# unified.net
KiCad netlist of a schematic drawn in EAGLE
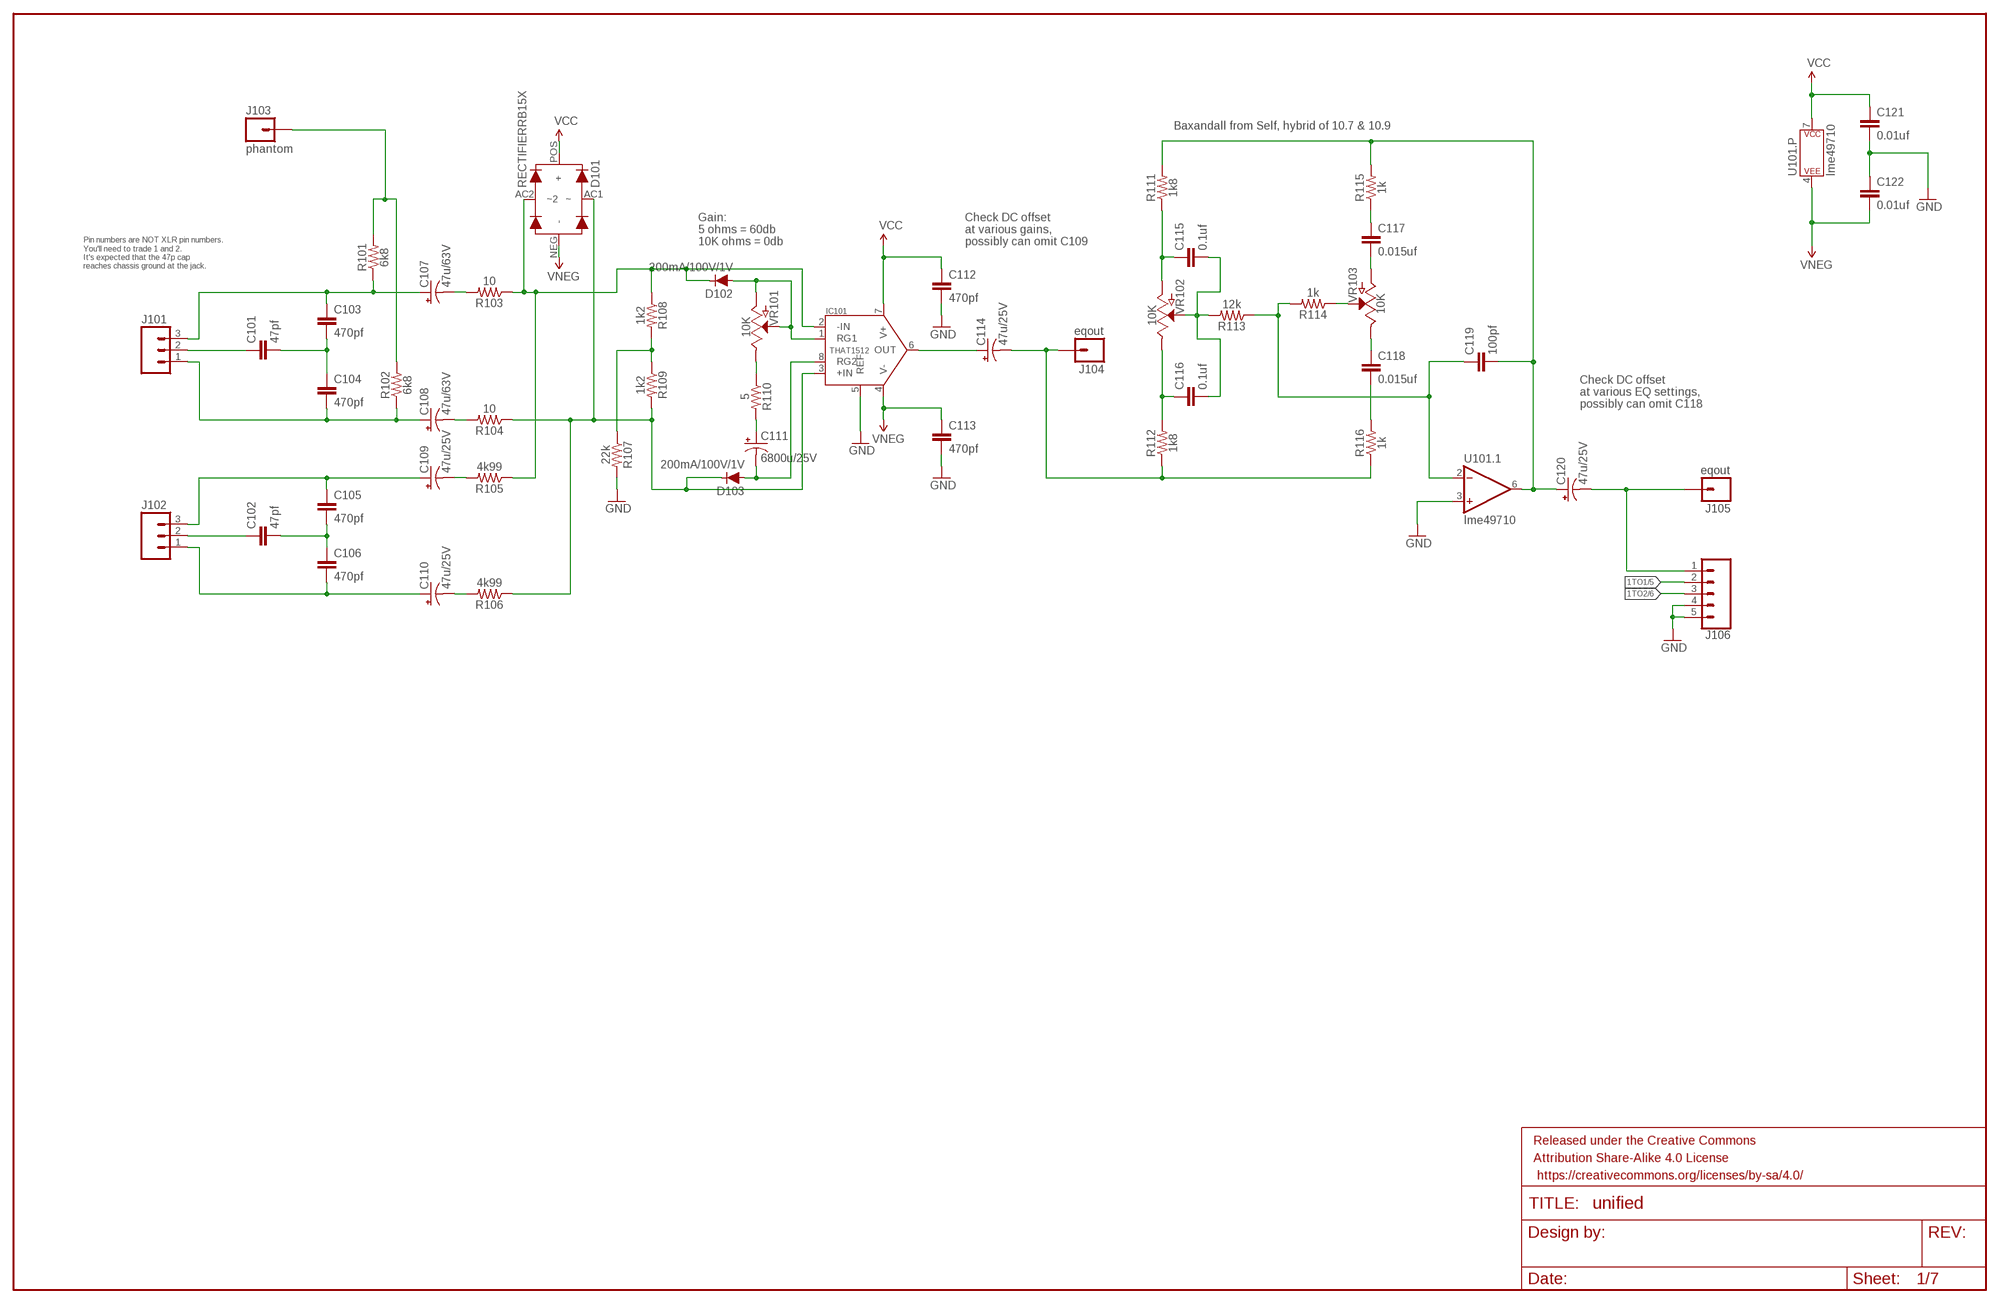
[diagram p0: schematic, sheet 1]
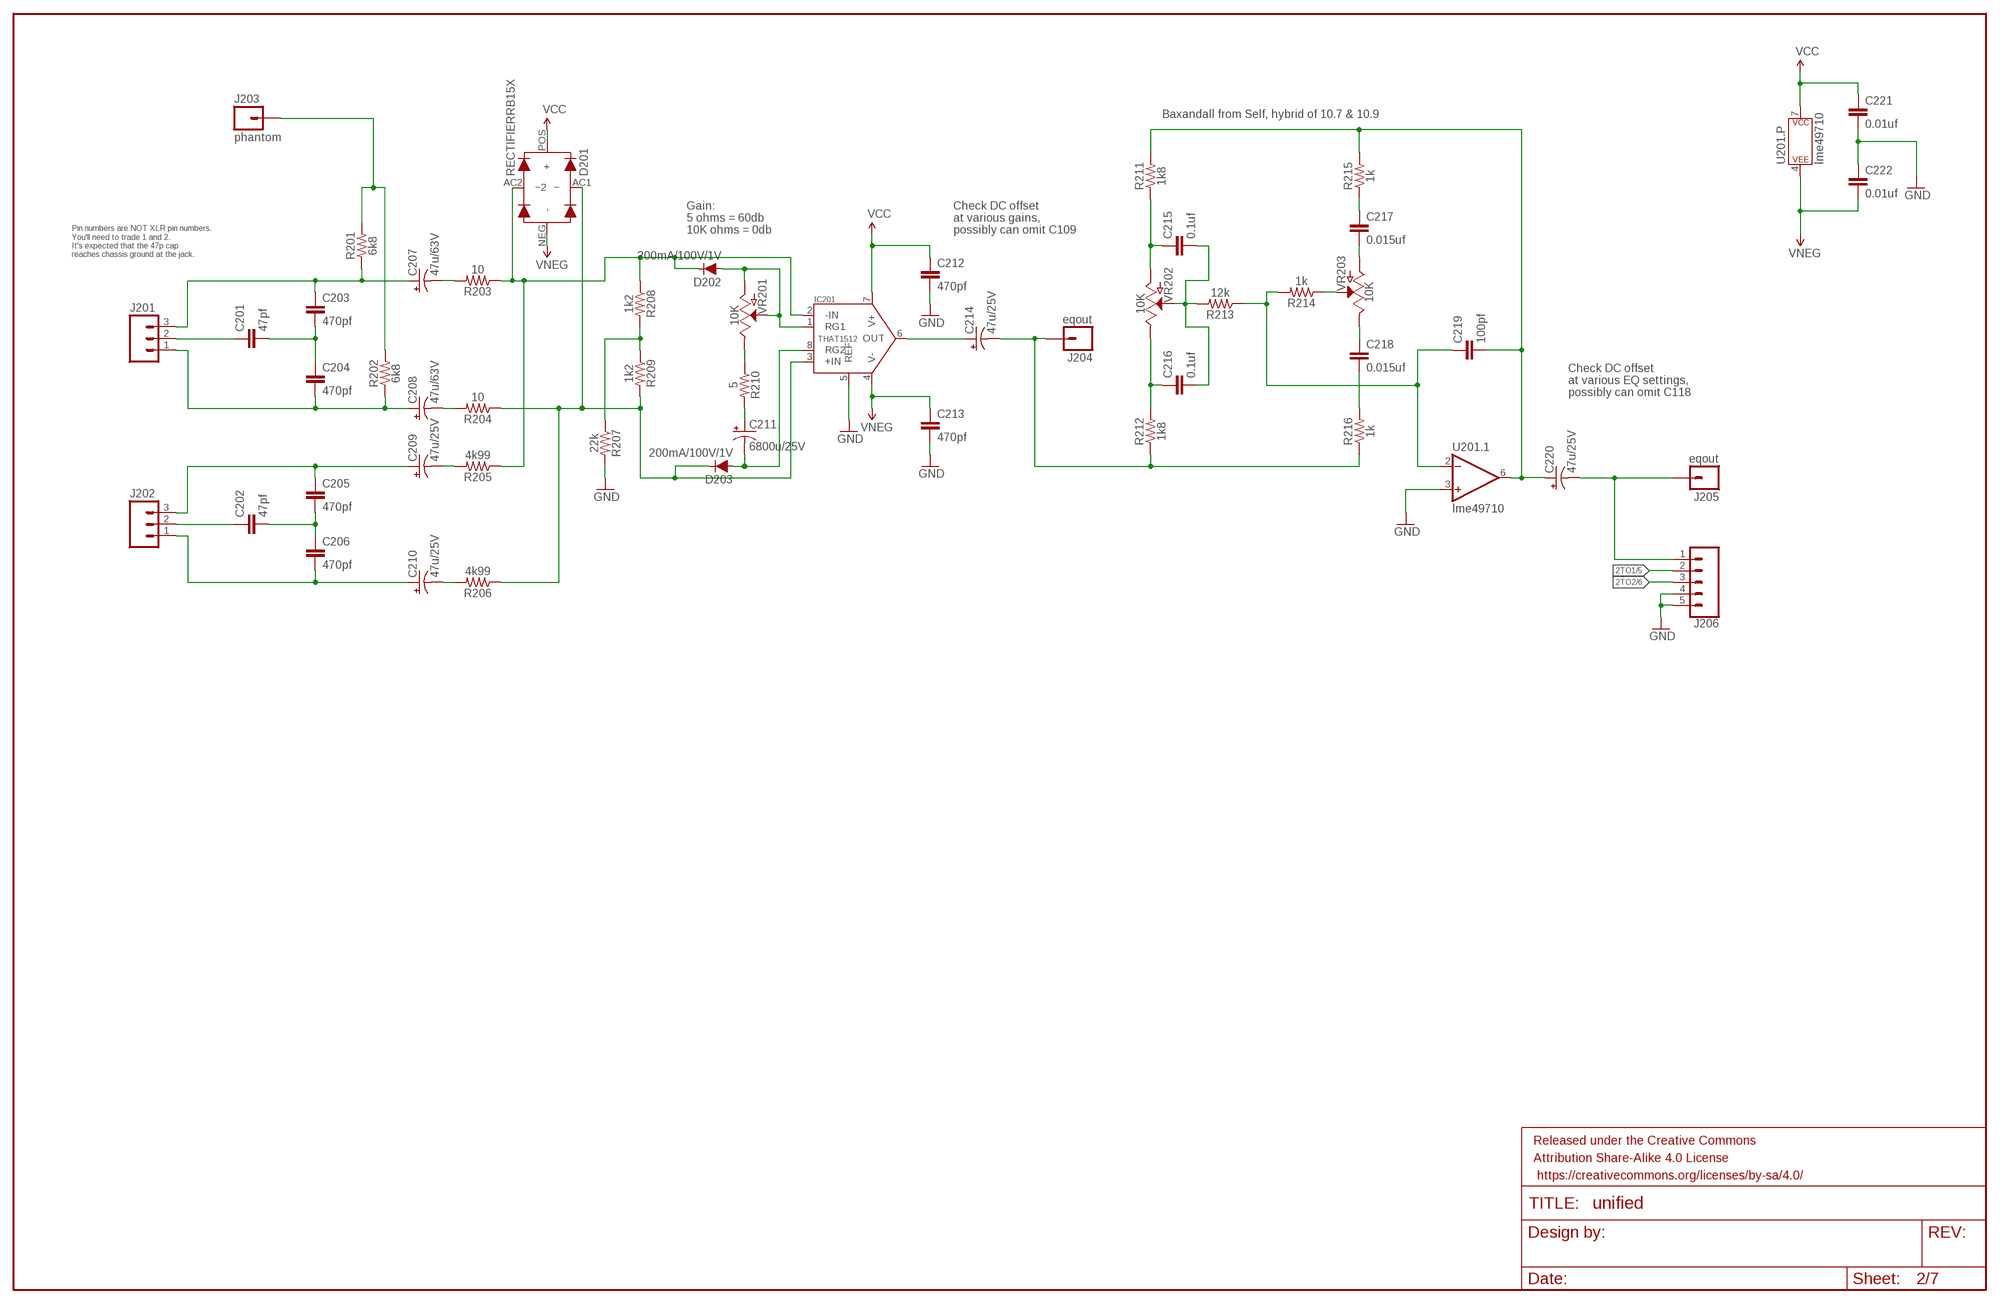
[diagram p1: schematic, sheet 2]
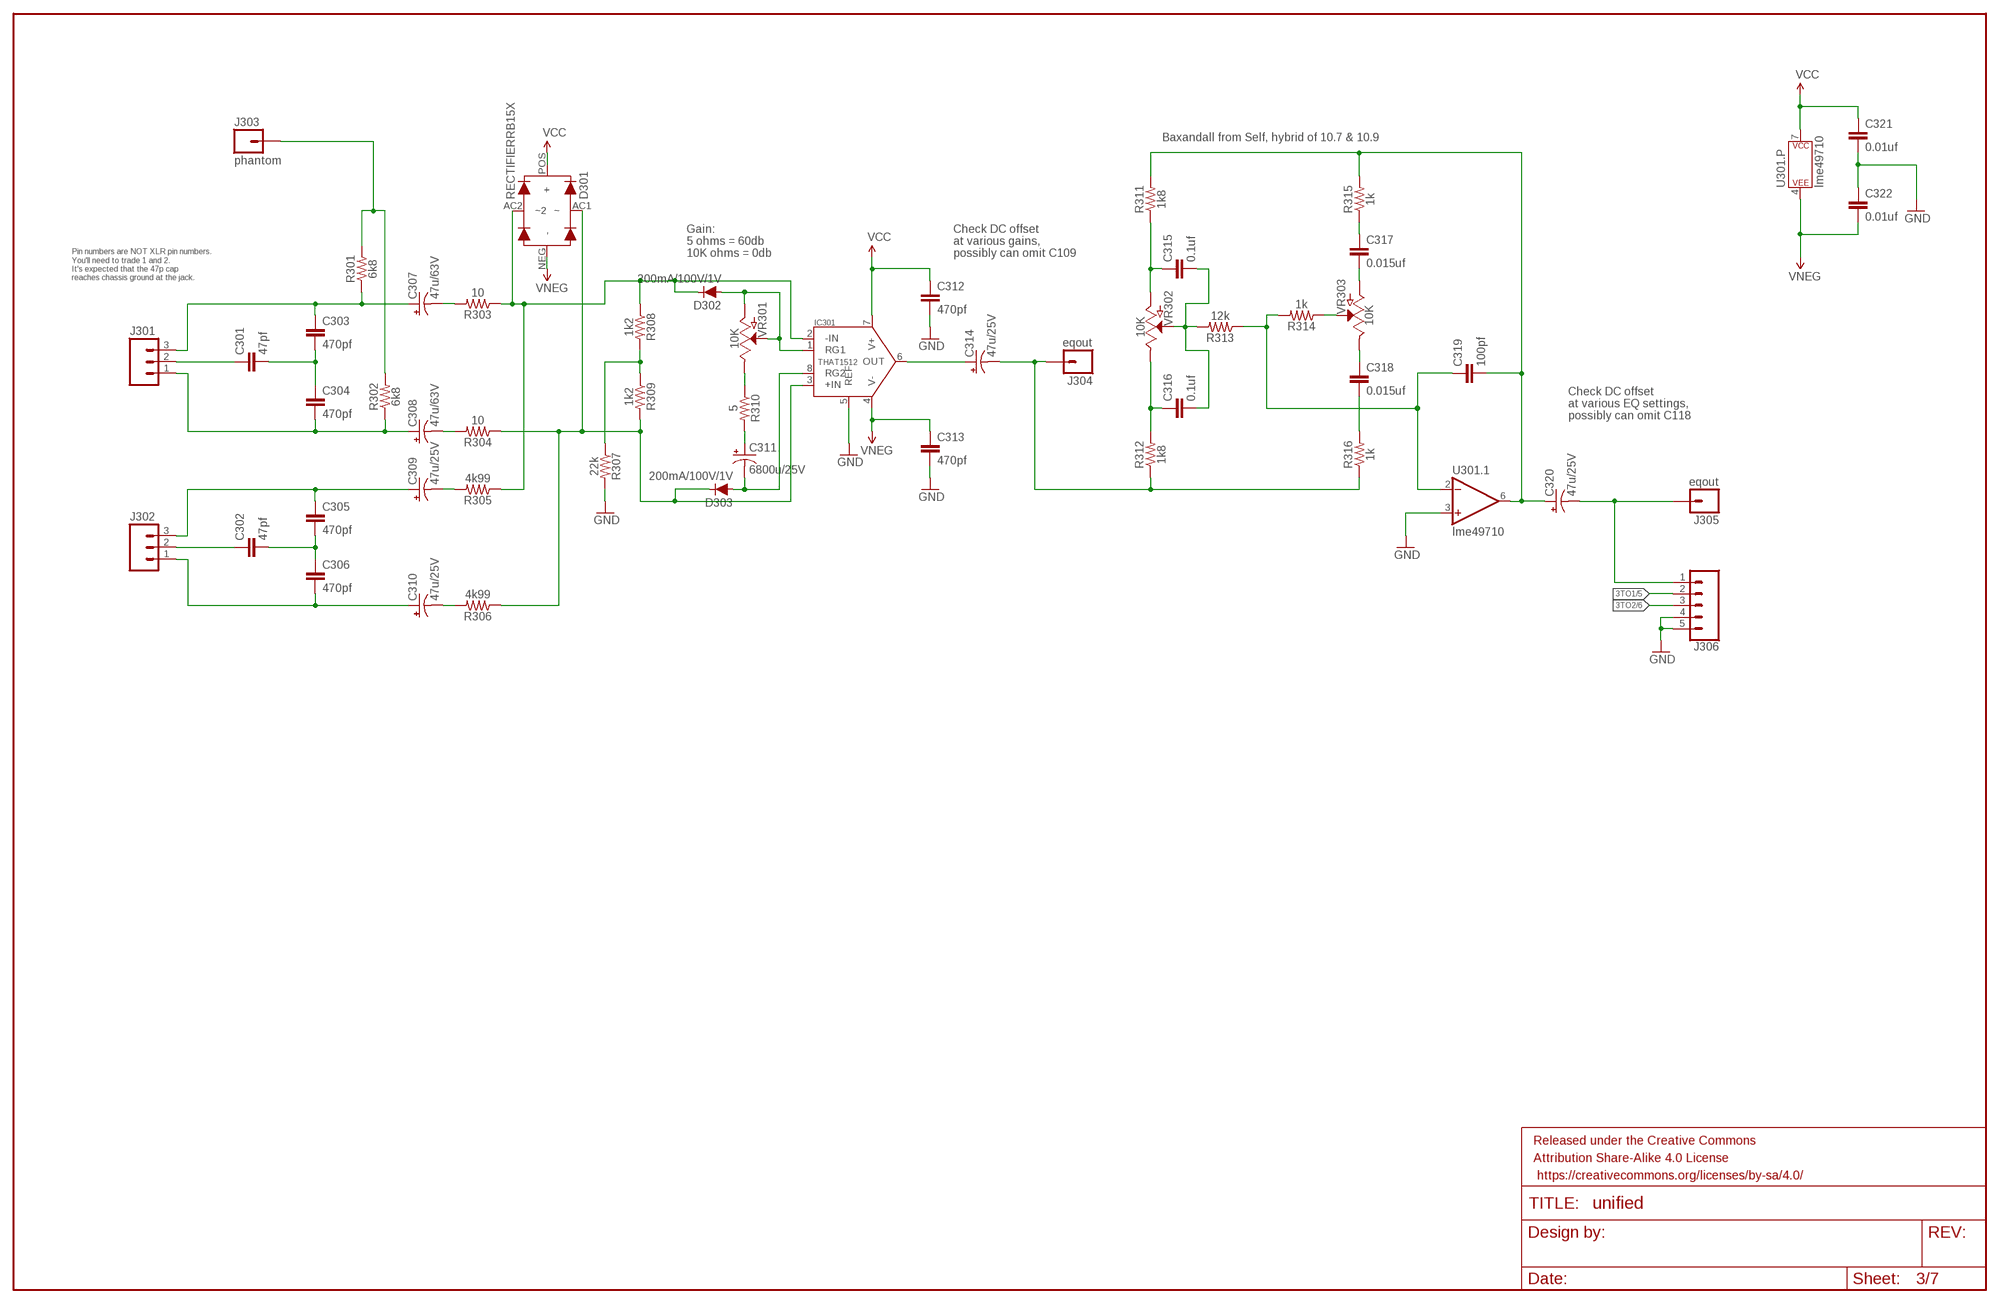
[diagram p2: schematic, sheet 3]
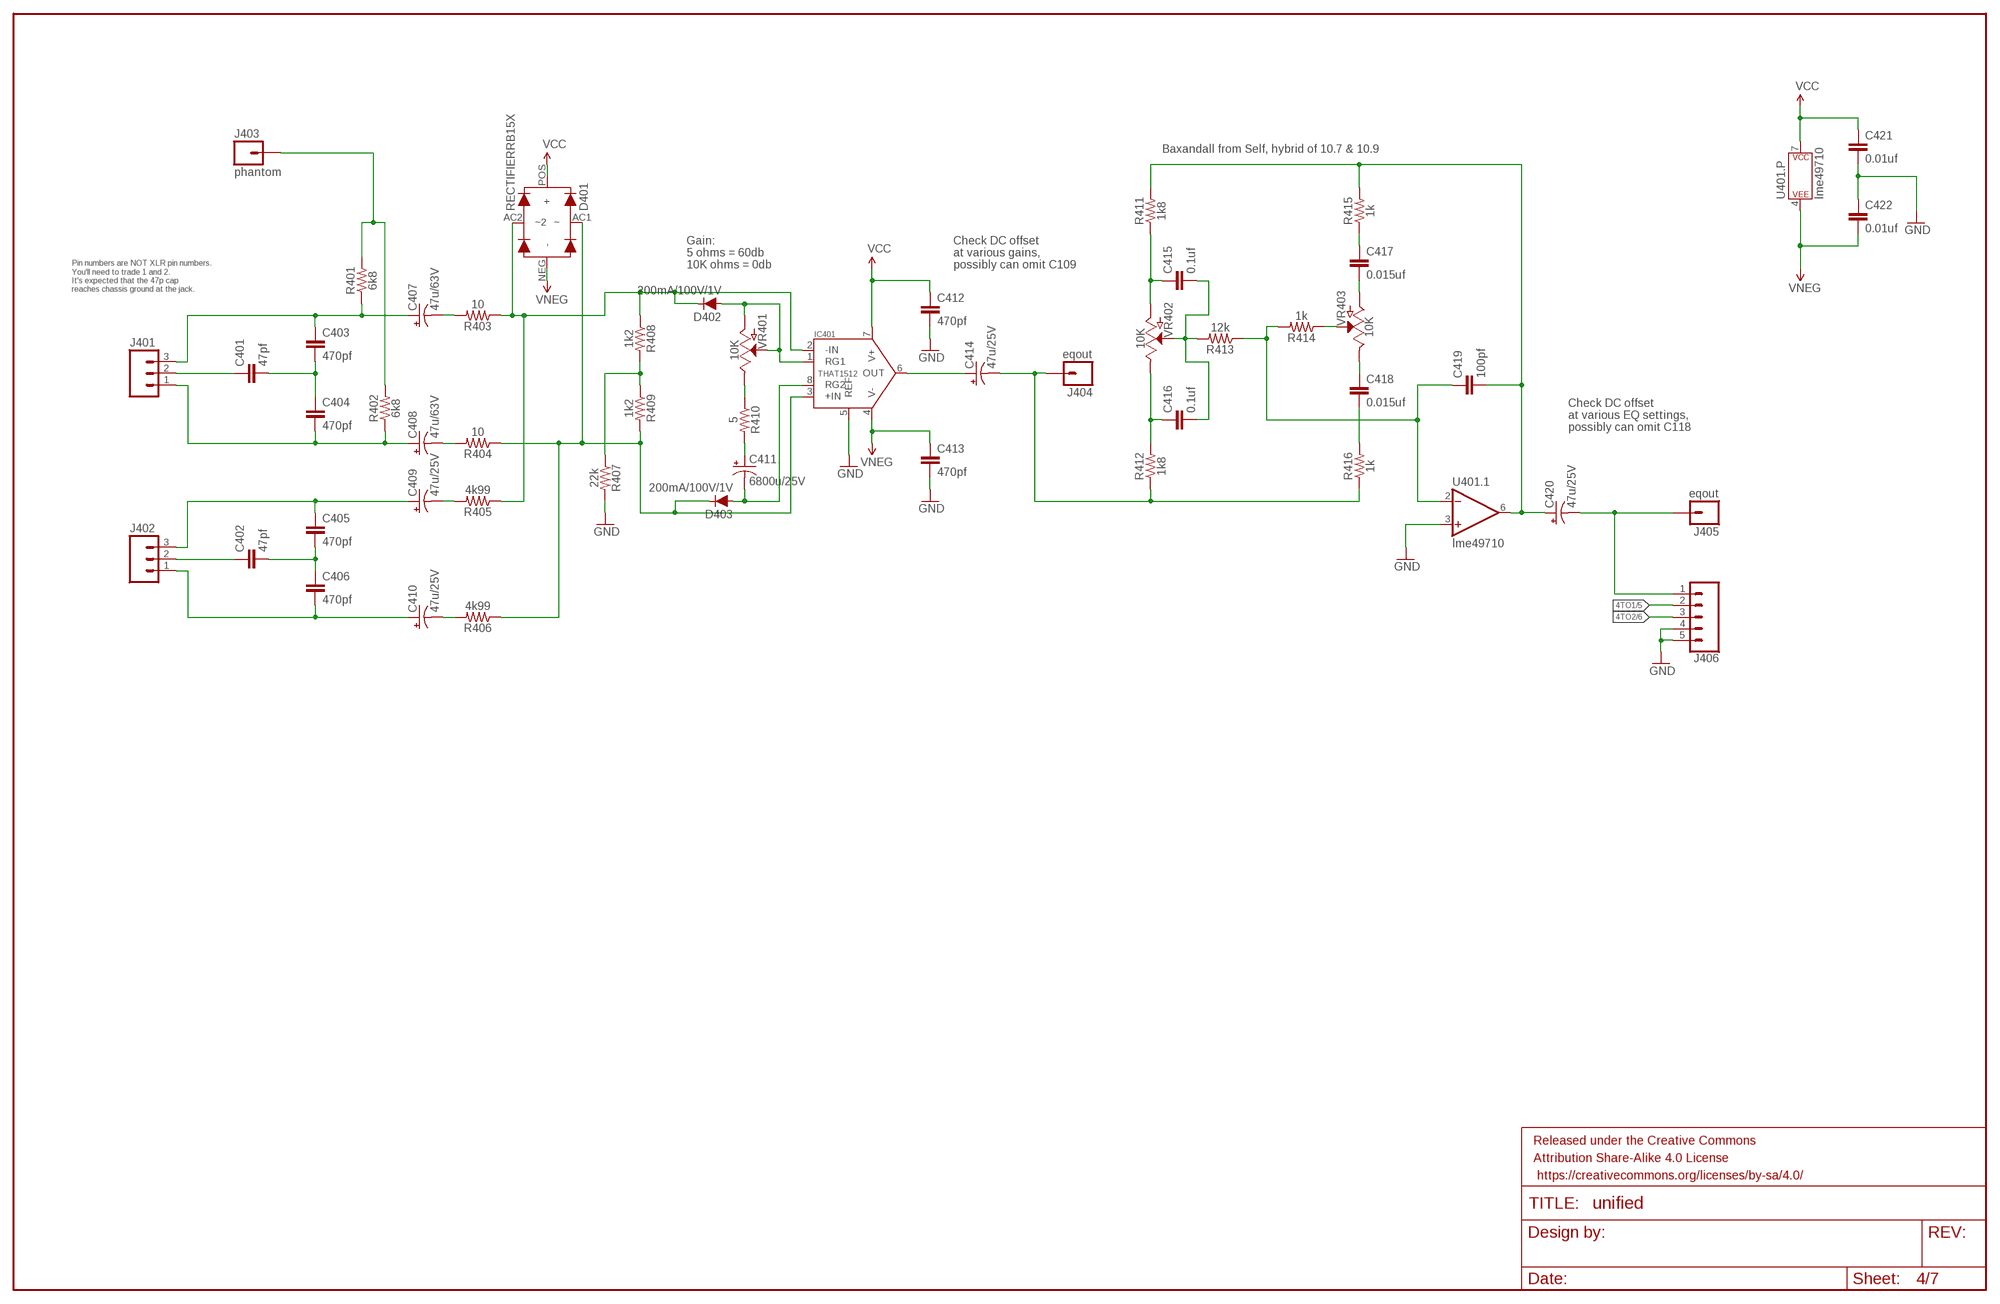
[diagram p3: schematic, sheet 4]
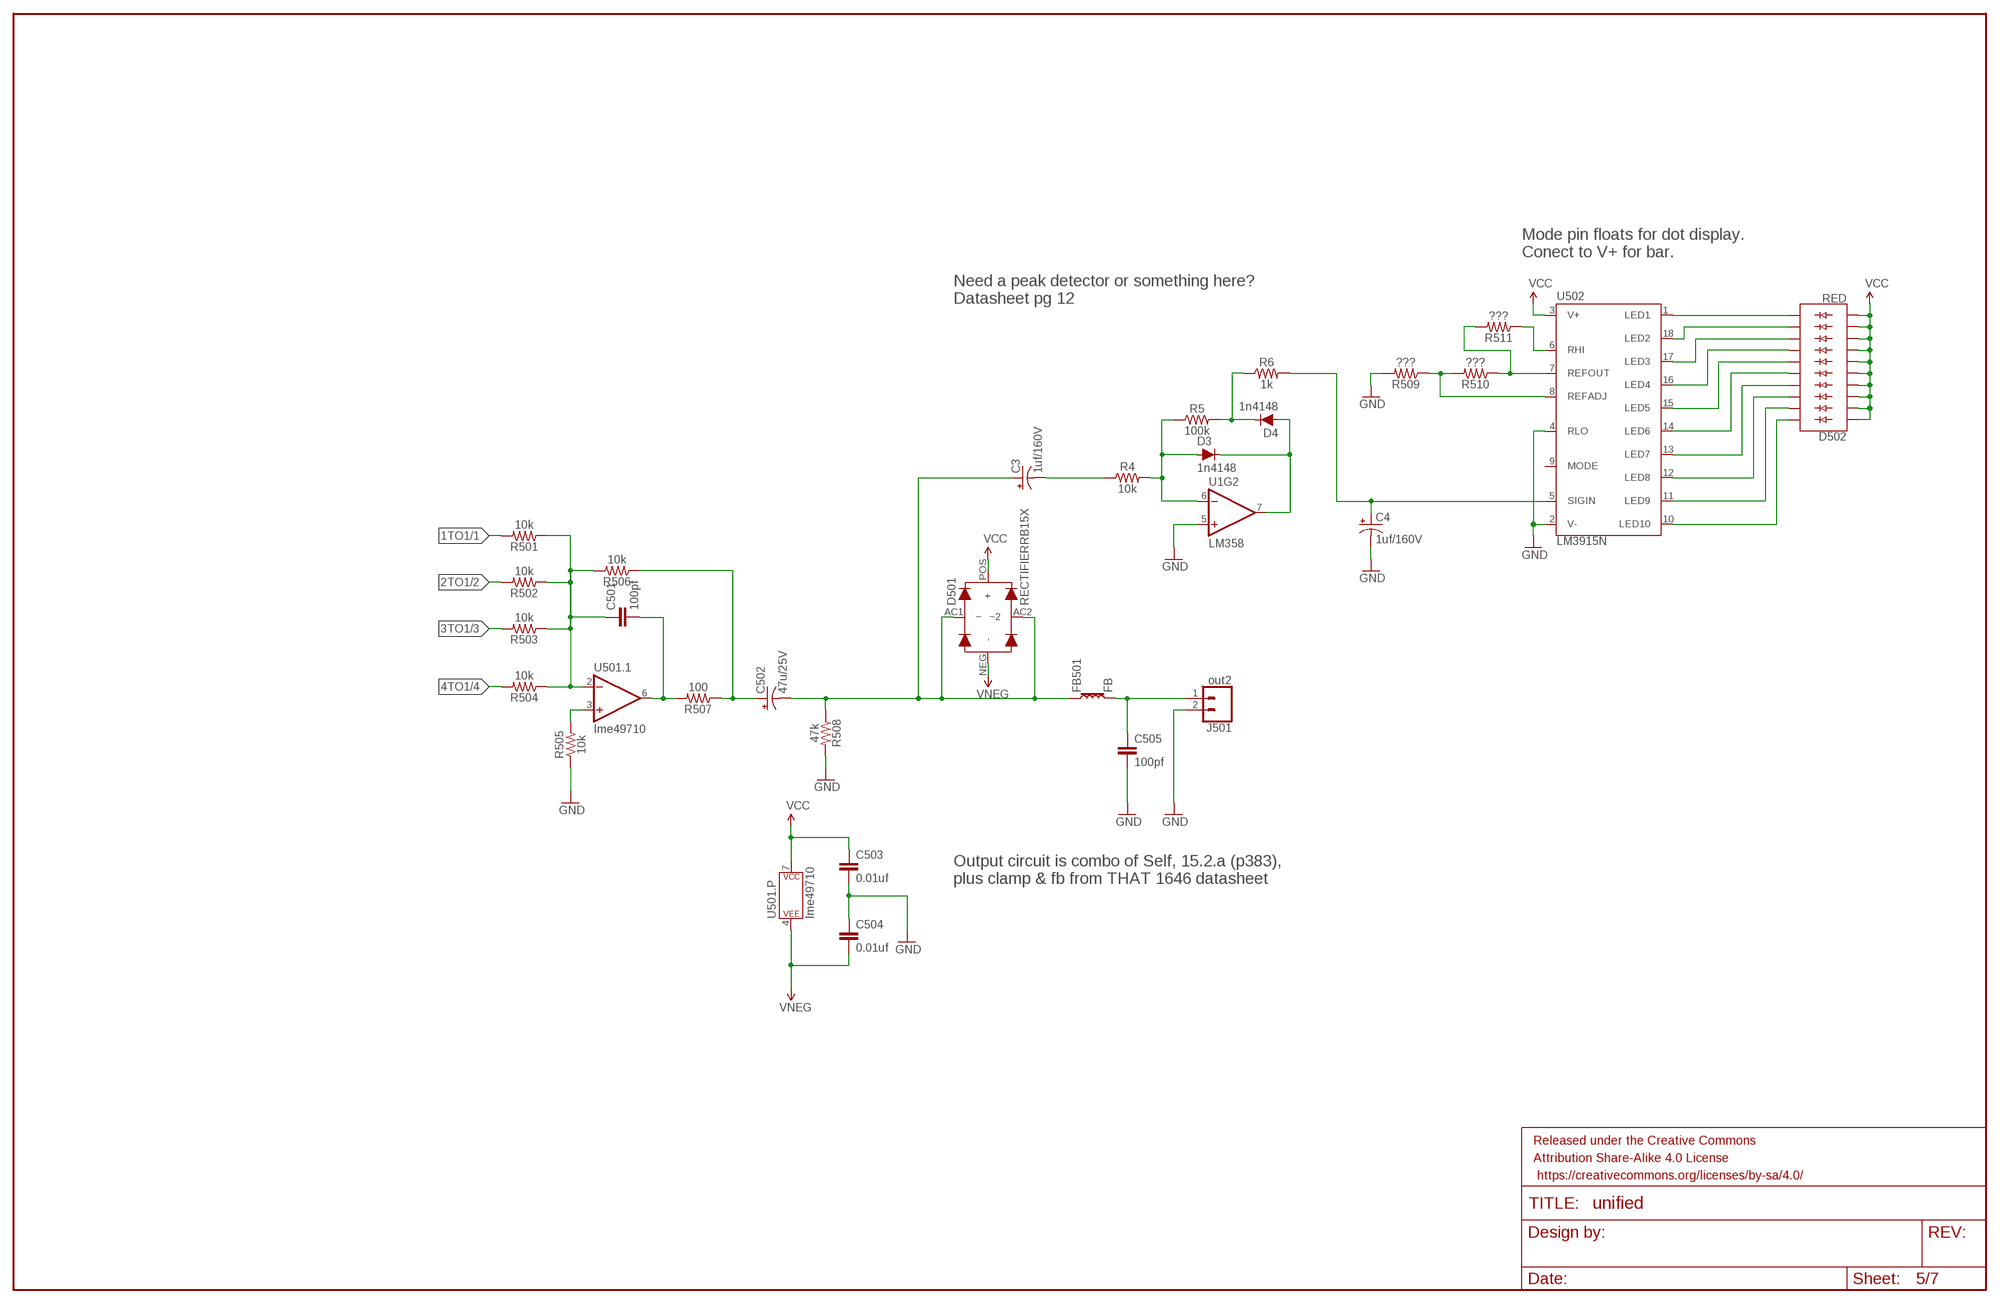
[diagram p4: schematic, sheet 5]
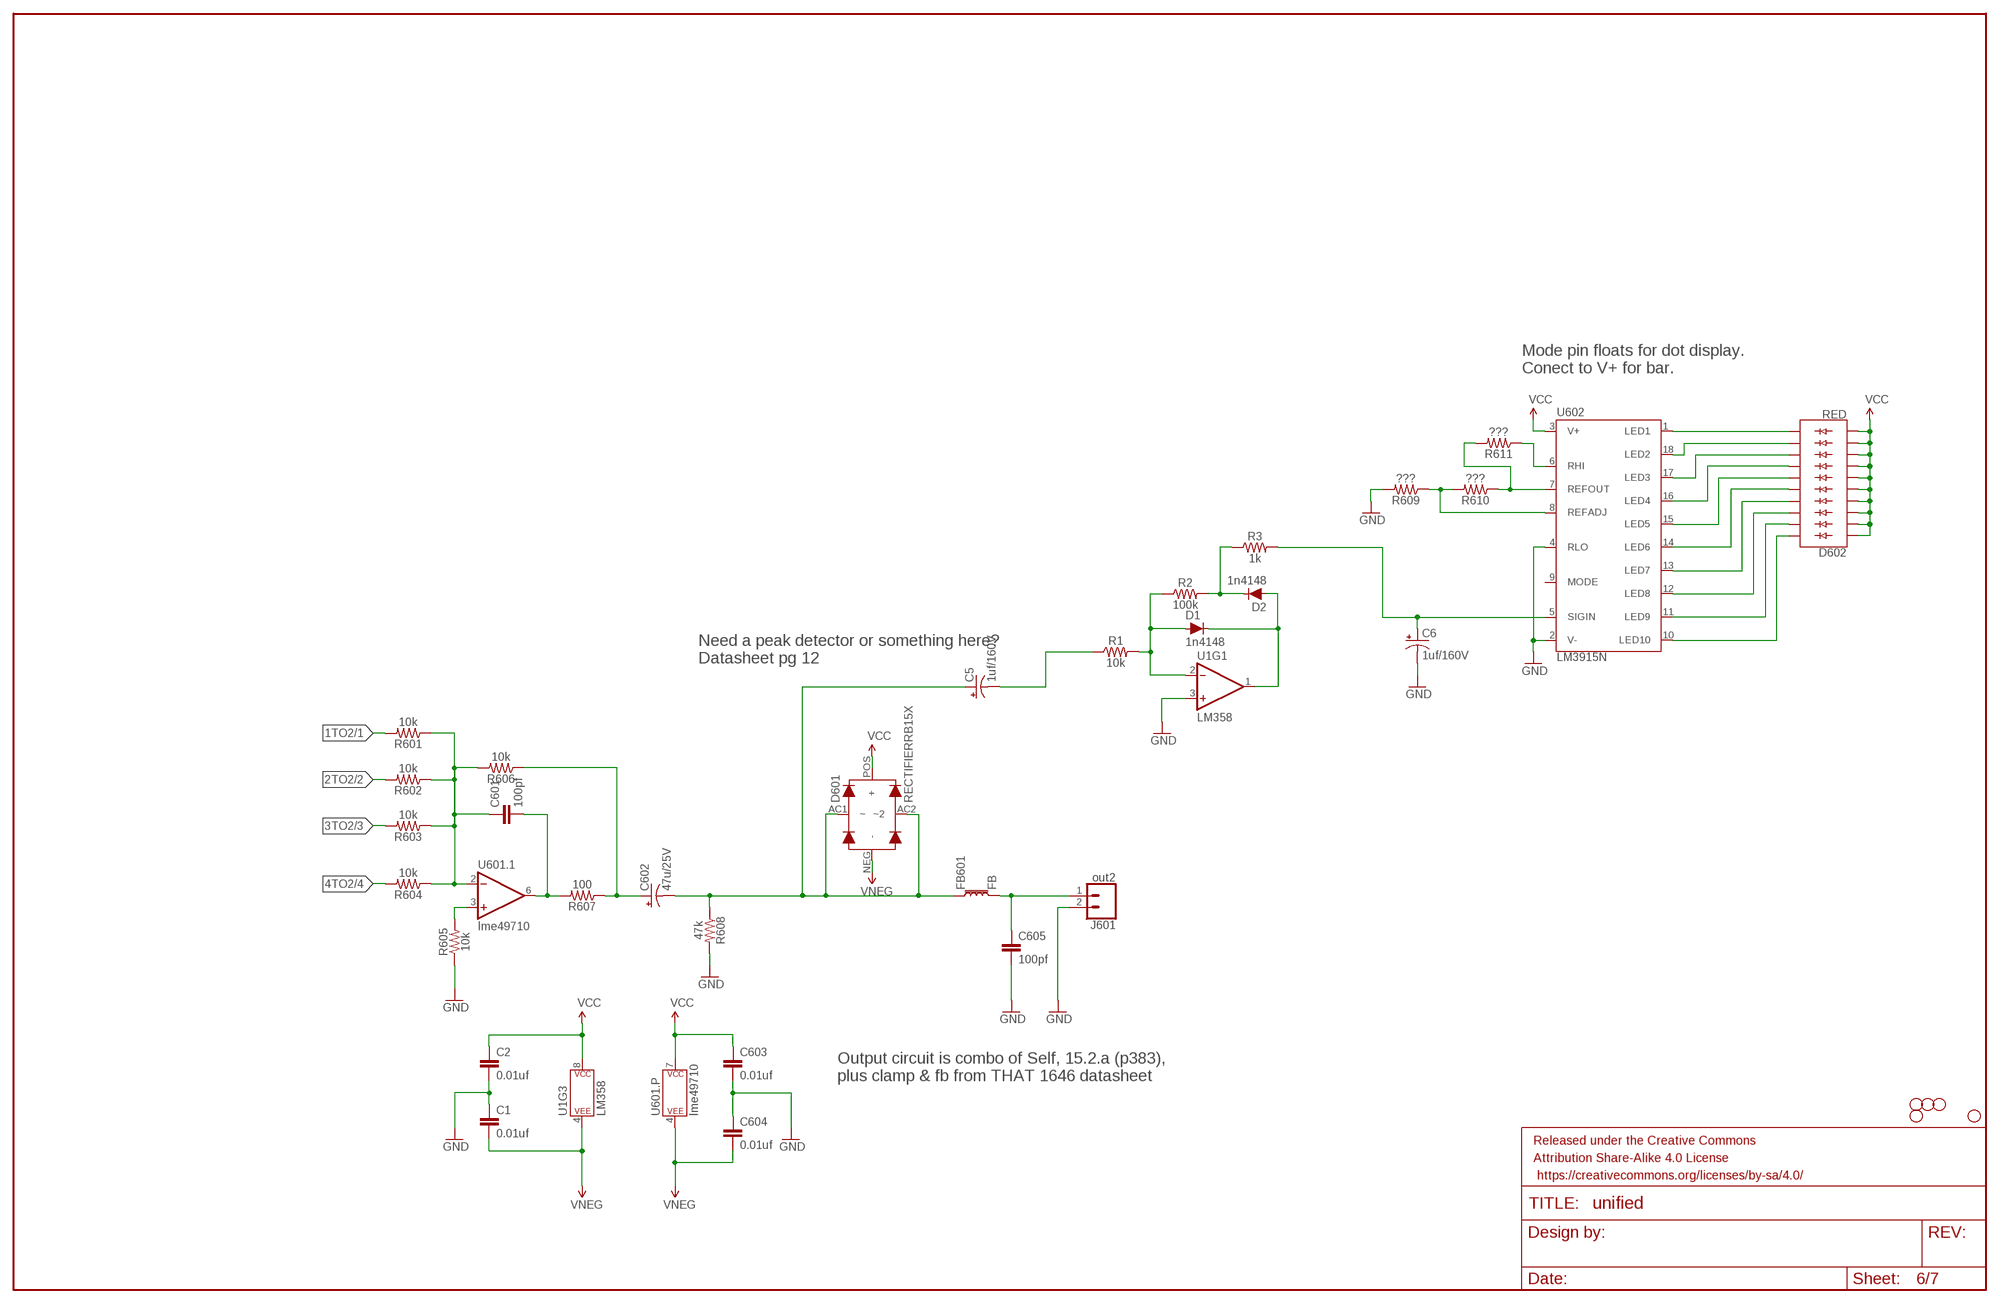
[diagram p5: schematic, sheet 6]
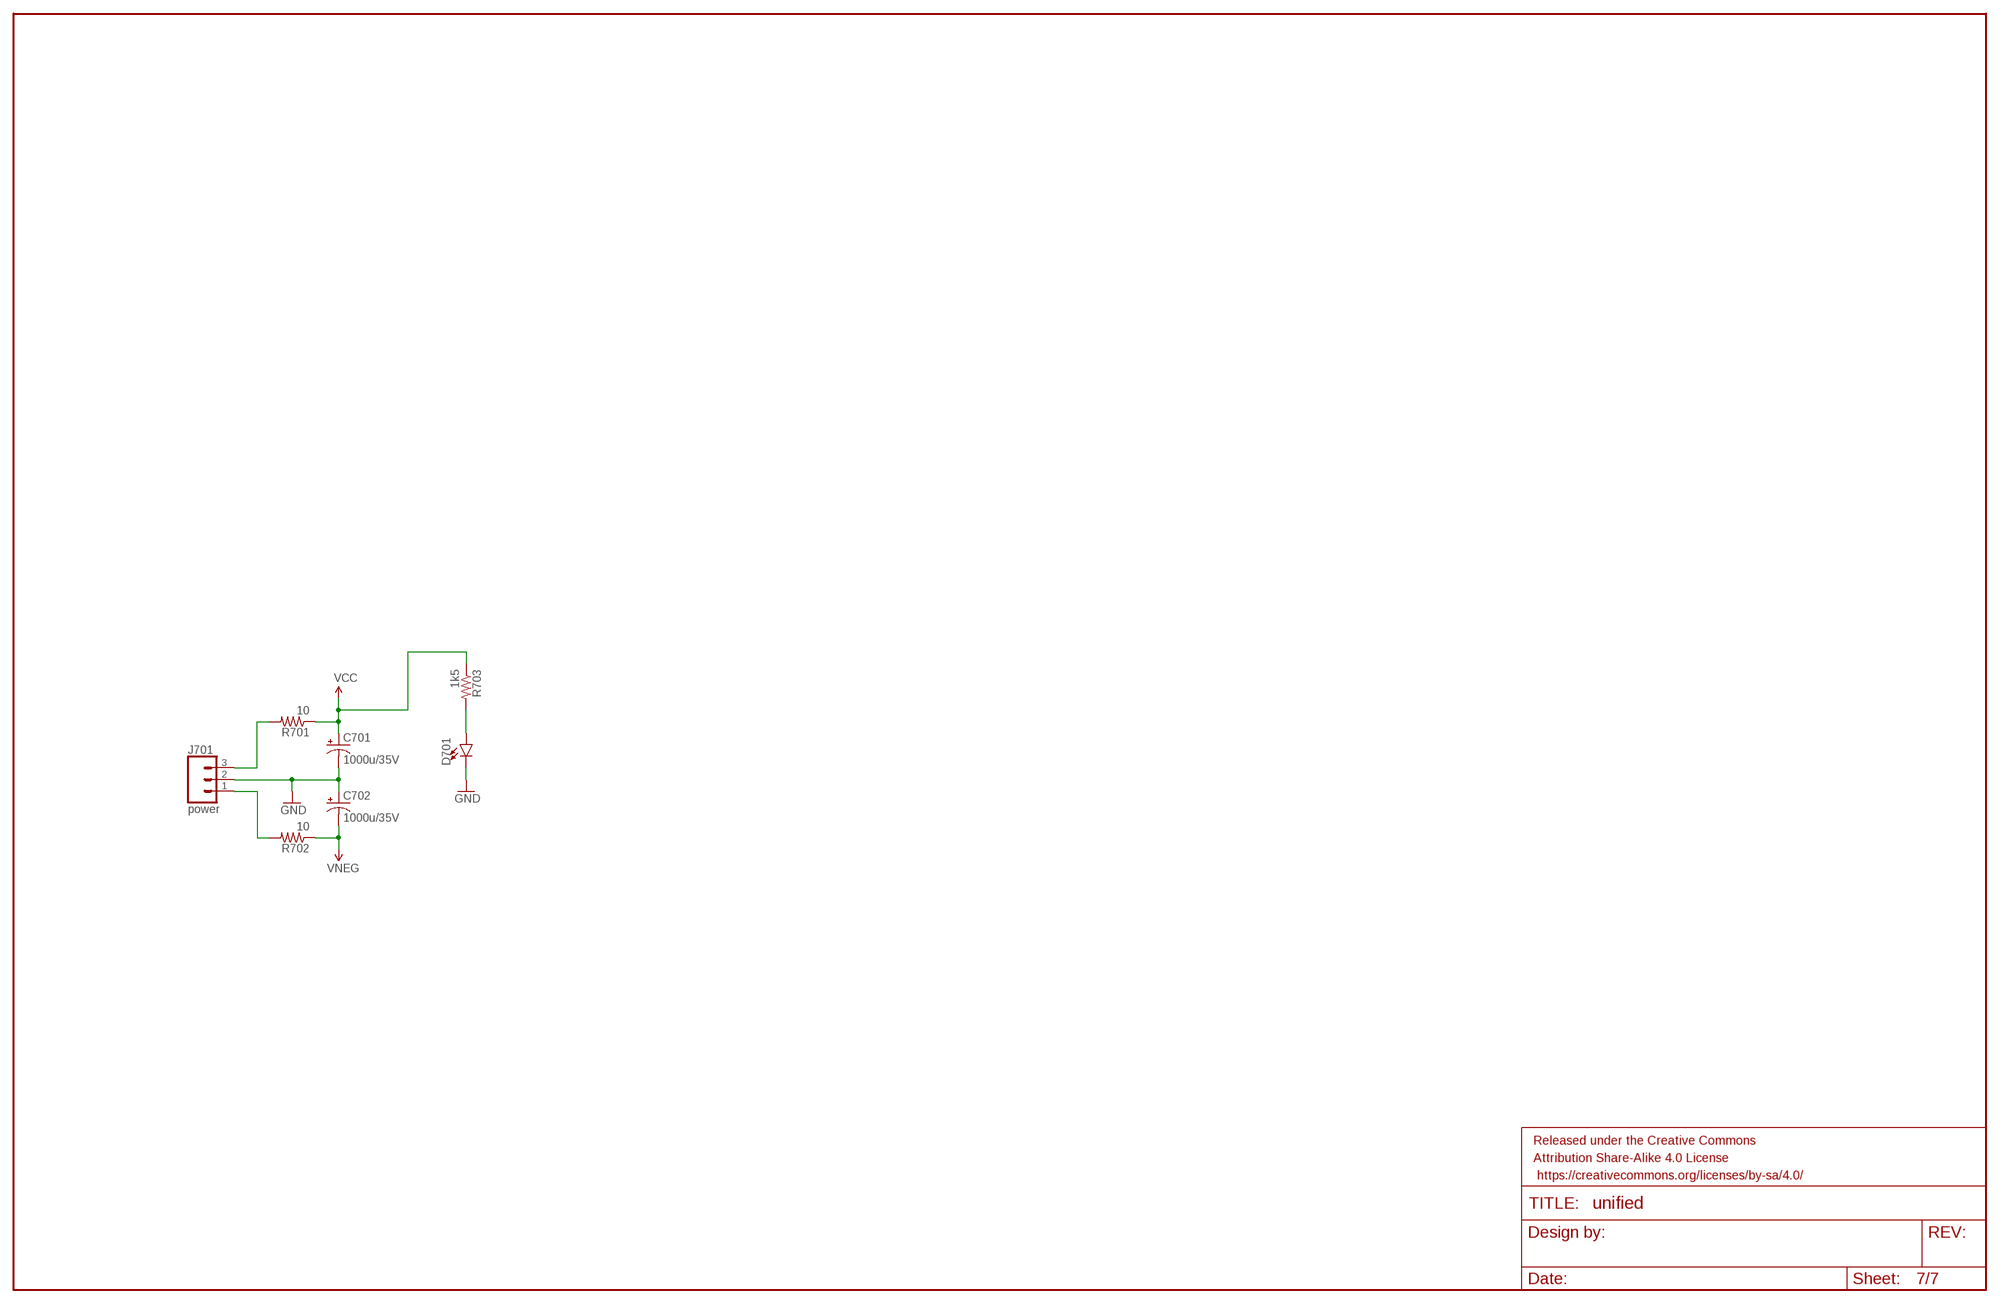
[diagram p6: schematic, sheet 7]

(export (version "E")
  (design (tool "Eeschema 10.0.6"))
  (components
    (comp (ref "C301")
      (value "47pf")
      (footprint "eagle-import:CAP-KEMET-GM-2.54LS")
      (libsource (lib "eagle-import") (part "CAP-CERAMIC47PF"))
    )
    (comp (ref "C302")
      (value "47pf")
      (footprint "eagle-import:CAP-KEMET-GM-2.54LS")
      (libsource (lib "eagle-import") (part "CAP-CERAMIC47PF"))
    )
    (comp (ref "C303")
      (value "470pf")
      (footprint "eagle-import:CAP-KEMET-GM-2.54LS")
      (libsource (lib "eagle-import") (part "CAP-CERAMIC470PF"))
    )
    (comp (ref "C304")
      (value "470pf")
      (footprint "eagle-import:CAP-KEMET-GM-2.54LS")
      (libsource (lib "eagle-import") (part "CAP-CERAMIC470PF"))
    )
    (comp (ref "C305")
      (value "470pf")
      (footprint "eagle-import:CAP-KEMET-GM-2.54LS")
      (libsource (lib "eagle-import") (part "CAP-CERAMIC470PF"))
    )
    (comp (ref "C306")
      (value "470pf")
      (footprint "eagle-import:CAP-KEMET-GM-2.54LS")
      (libsource (lib "eagle-import") (part "CAP-CERAMIC470PF"))
    )
    (comp (ref "C307")
      (value "47u/63V")
      (footprint "eagle-import:CAP-PANA-2LS-6DIAM")
      (libsource (lib "eagle-import") (part "CAP-LYTIC47U/63V"))
    )
    (comp (ref "C308")
      (value "47u/63V")
      (footprint "eagle-import:CAP-PANA-2LS-6DIAM")
      (libsource (lib "eagle-import") (part "CAP-LYTIC47U/63V"))
    )
    (comp (ref "C309")
      (value "47u/25V")
      (footprint "eagle-import:CAP-PANA-2LS-5DIAM")
      (libsource (lib "eagle-import") (part "CAP-LYTIC47U/25V"))
    )
    (comp (ref "C310")
      (value "47u/25V")
      (footprint "eagle-import:CAP-PANA-2LS-5DIAM")
      (libsource (lib "eagle-import") (part "CAP-LYTIC47U/25V"))
    )
    (comp (ref "C311")
      (value "6800u/25V")
      (footprint "eagle-import:CAP-PANA-5LS-12.5DIAM")
      (libsource (lib "eagle-import") (part "CAP-LYTIC6800U/10V"))
    )
    (comp (ref "C312")
      (value "470pf")
      (footprint "eagle-import:CAP-KEMET-GM-2.54LS")
      (libsource (lib "eagle-import") (part "CAP-CERAMIC470PF"))
    )
    (comp (ref "C313")
      (value "470pf")
      (footprint "eagle-import:CAP-KEMET-GM-2.54LS")
      (libsource (lib "eagle-import") (part "CAP-CERAMIC470PF"))
    )
    (comp (ref "C314")
      (value "47u/25V")
      (footprint "eagle-import:CAP-PANA-2LS-5DIAM")
      (libsource (lib "eagle-import") (part "CAP-LYTIC47U/25V"))
    )
    (comp (ref "C315")
      (value "0.1uf")
      (footprint "eagle-import:WIMA-MKS2-2.5X7.2")
      (libsource (lib "eagle-import") (part "WIMA-MKS20.1UF"))
    )
    (comp (ref "C316")
      (value "0.1uf")
      (footprint "eagle-import:WIMA-MKS2-2.5X7.2")
      (libsource (lib "eagle-import") (part "WIMA-MKS20.1UF"))
    )
    (comp (ref "C317")
      (value "0.015uf")
      (footprint "eagle-import:WIMA-MKS2-2.5X7.2")
      (libsource (lib "eagle-import") (part "WIMA-MKS20.015UF"))
    )
    (comp (ref "C318")
      (value "0.015uf")
      (footprint "eagle-import:WIMA-MKS2-2.5X7.2")
      (libsource (lib "eagle-import") (part "WIMA-MKS20.015UF"))
    )
    (comp (ref "C319")
      (value "100pf")
      (footprint "eagle-import:CAP-KEMET-GM-2.54LS")
      (libsource (lib "eagle-import") (part "CAP-CERAMIC100PF"))
    )
    (comp (ref "C320")
      (value "47u/25V")
      (footprint "eagle-import:CAP-PANA-2LS-5DIAM")
      (libsource (lib "eagle-import") (part "CAP-LYTIC47U/25V"))
    )
    (comp (ref "C321")
      (value "0.01uf")
      (footprint "eagle-import:WIMA-MKS2-2.5X7.2")
      (libsource (lib "eagle-import") (part "WIMA-MKS20.01UF"))
    )
    (comp (ref "C322")
      (value "0.01uf")
      (footprint "eagle-import:WIMA-MKS2-2.5X7.2")
      (libsource (lib "eagle-import") (part "WIMA-MKS20.01UF"))
    )
    (comp (ref "D301")
      (value "RECTIFIERRB15X")
      (footprint "eagle-import:SM-RECTIFIER")
      (libsource (lib "eagle-import") (part "RECTIFIERRB15X"))
    )
    (comp (ref "D302")
      (value "200mA/100V/1V")
      (footprint "eagle-import:DIODE-1N4148")
      (libsource (lib "eagle-import") (part "DIODE-1N4148"))
    )
    (comp (ref "D303")
      (value "200mA/100V/1V")
      (footprint "eagle-import:DIODE-1N4148")
      (libsource (lib "eagle-import") (part "DIODE-1N4148"))
    )
    (comp (ref "FRAME301")
      (value "FRAME-LEDGER")
      (footprint "eagle-import:CREATIVE_COMMONS")
      (libsource (lib "eagle-import") (part "FRAME-LEDGER"))
    )
    (comp (ref "IC301")
      (value "THAT1512")
      (footprint "eagle-import:DIP08-KIT")
      (libsource (lib "eagle-import") (part "THAT151X"))
    )
    (comp (ref "J301")
      (value "M031X03_NO_SILK")
      (footprint "eagle-import:1X03_NO_SILK@1")
      (libsource (lib "eagle-import") (part "M031X03_NO_SILK"))
    )
    (comp (ref "J302")
      (value "M031X03_NO_SILK")
      (footprint "eagle-import:1X03_NO_SILK@1")
      (libsource (lib "eagle-import") (part "M031X03_NO_SILK"))
    )
    (comp (ref "J303")
      (value "phantom")
      (footprint "eagle-import:1X01NS-KIT")
      (libsource (lib "eagle-import") (part "M01NOSILK-KIT"))
    )
    (comp (ref "J304")
      (value "eqout")
      (footprint "eagle-import:1X01NS-KIT")
      (libsource (lib "eagle-import") (part "M01NOSILK-KIT"))
    )
    (comp (ref "J305")
      (value "eqout")
      (footprint "eagle-import:1X01NS-KIT")
      (libsource (lib "eagle-import") (part "M01NOSILK-KIT"))
    )
    (comp (ref "J306")
      (value "CONN_05PTH_LONGPADS")
      (footprint "eagle-import:1X05_LONGPADS")
      (libsource (lib "eagle-import") (part "CONN_05PTH_LONGPADS"))
    )
    (comp (ref "R301")
      (value "6k8")
      (footprint "eagle-import:AXIAL-0.3")
      (libsource (lib "eagle-import") (part "RESISTOR"))
    )
    (comp (ref "R302")
      (value "6k8")
      (footprint "eagle-import:AXIAL-0.3")
      (libsource (lib "eagle-import") (part "RESISTOR"))
    )
    (comp (ref "R303")
      (value "10")
      (footprint "eagle-import:AXIAL-0.3")
      (libsource (lib "eagle-import") (part "RESISTOR"))
    )
    (comp (ref "R304")
      (value "10")
      (footprint "eagle-import:AXIAL-0.3")
      (libsource (lib "eagle-import") (part "RESISTOR"))
    )
    (comp (ref "R305")
      (value "4k99")
      (footprint "eagle-import:AXIAL-0.3")
      (libsource (lib "eagle-import") (part "RESISTOR"))
    )
    (comp (ref "R306")
      (value "4k99")
      (footprint "eagle-import:AXIAL-0.3")
      (libsource (lib "eagle-import") (part "RESISTOR"))
    )
    (comp (ref "R307")
      (value "22k")
      (footprint "eagle-import:AXIAL-0.3")
      (libsource (lib "eagle-import") (part "RESISTOR"))
    )
    (comp (ref "R308")
      (value "1k2")
      (footprint "eagle-import:AXIAL-0.3")
      (libsource (lib "eagle-import") (part "RESISTOR"))
    )
    (comp (ref "R309")
      (value "1k2")
      (footprint "eagle-import:AXIAL-0.3")
      (libsource (lib "eagle-import") (part "RESISTOR"))
    )
    (comp (ref "R310")
      (value "5")
      (footprint "eagle-import:AXIAL-0.3")
      (libsource (lib "eagle-import") (part "RESISTOR"))
    )
    (comp (ref "R311")
      (value "1k8")
      (footprint "eagle-import:AXIAL-0.3")
      (libsource (lib "eagle-import") (part "RESISTOR"))
    )
    (comp (ref "R312")
      (value "1k8")
      (footprint "eagle-import:AXIAL-0.3")
      (libsource (lib "eagle-import") (part "RESISTOR"))
    )
    (comp (ref "R313")
      (value "12k")
      (footprint "eagle-import:AXIAL-0.3")
      (libsource (lib "eagle-import") (part "RESISTOR"))
    )
    (comp (ref "R314")
      (value "1k")
      (footprint "eagle-import:AXIAL-0.3")
      (libsource (lib "eagle-import") (part "RESISTOR"))
    )
    (comp (ref "R315")
      (value "1k")
      (footprint "eagle-import:AXIAL-0.3")
      (libsource (lib "eagle-import") (part "RESISTOR"))
    )
    (comp (ref "R316")
      (value "1k")
      (footprint "eagle-import:AXIAL-0.3")
      (libsource (lib "eagle-import") (part "RESISTOR"))
    )
    (comp (ref "U301")
      (value "lme49710")
      (footprint "eagle-import:DIP08-KIT")
      (libsource (lib "eagle-import") (part "OPAMPLME49710"))
    )
    (comp (ref "VR301")
      (value "10K")
      (footprint "eagle-import:ROT-SW-POT")
      (libsource (lib "eagle-import") (part "POTROT-SW-POT"))
    )
    (comp (ref "VR302")
      (value "10K")
      (footprint "eagle-import:ALPHA-RV24AF40-POT")
      (libsource (lib "eagle-import") (part "POT10K-VERTPIN"))
    )
    (comp (ref "VR303")
      (value "10K")
      (footprint "eagle-import:ALPHA-RV24AF40-POT")
      (libsource (lib "eagle-import") (part "POT10K-VERTPIN"))
    )
    (comp (ref "C101")
      (value "47pf")
      (footprint "eagle-import:CAP-KEMET-GM-2.54LS")
      (libsource (lib "eagle-import") (part "CAP-CERAMIC47PF"))
    )
    (comp (ref "C102")
      (value "47pf")
      (footprint "eagle-import:CAP-KEMET-GM-2.54LS")
      (libsource (lib "eagle-import") (part "CAP-CERAMIC47PF"))
    )
    (comp (ref "C103")
      (value "470pf")
      (footprint "eagle-import:CAP-KEMET-GM-2.54LS")
      (libsource (lib "eagle-import") (part "CAP-CERAMIC470PF"))
    )
    (comp (ref "C104")
      (value "470pf")
      (footprint "eagle-import:CAP-KEMET-GM-2.54LS")
      (libsource (lib "eagle-import") (part "CAP-CERAMIC470PF"))
    )
    (comp (ref "C105")
      (value "470pf")
      (footprint "eagle-import:CAP-KEMET-GM-2.54LS")
      (libsource (lib "eagle-import") (part "CAP-CERAMIC470PF"))
    )
    (comp (ref "C106")
      (value "470pf")
      (footprint "eagle-import:CAP-KEMET-GM-2.54LS")
      (libsource (lib "eagle-import") (part "CAP-CERAMIC470PF"))
    )
    (comp (ref "C107")
      (value "47u/63V")
      (footprint "eagle-import:CAP-PANA-2LS-6DIAM")
      (libsource (lib "eagle-import") (part "CAP-LYTIC47U/63V"))
    )
    (comp (ref "C108")
      (value "47u/63V")
      (footprint "eagle-import:CAP-PANA-2LS-6DIAM")
      (libsource (lib "eagle-import") (part "CAP-LYTIC47U/63V"))
    )
    (comp (ref "C109")
      (value "47u/25V")
      (footprint "eagle-import:CAP-PANA-2LS-5DIAM")
      (libsource (lib "eagle-import") (part "CAP-LYTIC47U/25V"))
    )
    (comp (ref "C110")
      (value "47u/25V")
      (footprint "eagle-import:CAP-PANA-2LS-5DIAM")
      (libsource (lib "eagle-import") (part "CAP-LYTIC47U/25V"))
    )
    (comp (ref "C111")
      (value "6800u/25V")
      (footprint "eagle-import:CAP-PANA-5LS-12.5DIAM")
      (libsource (lib "eagle-import") (part "CAP-LYTIC6800U/10V"))
    )
    (comp (ref "C112")
      (value "470pf")
      (footprint "eagle-import:CAP-KEMET-GM-2.54LS")
      (libsource (lib "eagle-import") (part "CAP-CERAMIC470PF"))
    )
    (comp (ref "C113")
      (value "470pf")
      (footprint "eagle-import:CAP-KEMET-GM-2.54LS")
      (libsource (lib "eagle-import") (part "CAP-CERAMIC470PF"))
    )
    (comp (ref "C114")
      (value "47u/25V")
      (footprint "eagle-import:CAP-PANA-2LS-5DIAM")
      (libsource (lib "eagle-import") (part "CAP-LYTIC47U/25V"))
    )
    (comp (ref "C115")
      (value "0.1uf")
      (footprint "eagle-import:WIMA-MKS2-2.5X7.2")
      (libsource (lib "eagle-import") (part "WIMA-MKS20.1UF"))
    )
    (comp (ref "C116")
      (value "0.1uf")
      (footprint "eagle-import:WIMA-MKS2-2.5X7.2")
      (libsource (lib "eagle-import") (part "WIMA-MKS20.1UF"))
    )
    (comp (ref "C117")
      (value "0.015uf")
      (footprint "eagle-import:WIMA-MKS2-2.5X7.2")
      (libsource (lib "eagle-import") (part "WIMA-MKS20.015UF"))
    )
    (comp (ref "C118")
      (value "0.015uf")
      (footprint "eagle-import:WIMA-MKS2-2.5X7.2")
      (libsource (lib "eagle-import") (part "WIMA-MKS20.015UF"))
    )
    (comp (ref "C119")
      (value "100pf")
      (footprint "eagle-import:CAP-KEMET-GM-2.54LS")
      (libsource (lib "eagle-import") (part "CAP-CERAMIC100PF"))
    )
    (comp (ref "C120")
      (value "47u/25V")
      (footprint "eagle-import:CAP-PANA-2LS-5DIAM")
      (libsource (lib "eagle-import") (part "CAP-LYTIC47U/25V"))
    )
    (comp (ref "C121")
      (value "0.01uf")
      (footprint "eagle-import:WIMA-MKS2-2.5X7.2")
      (libsource (lib "eagle-import") (part "WIMA-MKS20.01UF"))
    )
    (comp (ref "C122")
      (value "0.01uf")
      (footprint "eagle-import:WIMA-MKS2-2.5X7.2")
      (libsource (lib "eagle-import") (part "WIMA-MKS20.01UF"))
    )
    (comp (ref "D101")
      (value "RECTIFIERRB15X")
      (footprint "eagle-import:SM-RECTIFIER")
      (libsource (lib "eagle-import") (part "RECTIFIERRB15X"))
    )
    (comp (ref "D102")
      (value "200mA/100V/1V")
      (footprint "eagle-import:DIODE-1N4148")
      (libsource (lib "eagle-import") (part "DIODE-1N4148"))
    )
    (comp (ref "D103")
      (value "200mA/100V/1V")
      (footprint "eagle-import:DIODE-1N4148")
      (libsource (lib "eagle-import") (part "DIODE-1N4148"))
    )
    (comp (ref "FRAME101")
      (value "FRAME-LEDGER")
      (footprint "eagle-import:CREATIVE_COMMONS")
      (libsource (lib "eagle-import") (part "FRAME-LEDGER"))
    )
    (comp (ref "IC101")
      (value "THAT1512")
      (footprint "eagle-import:DIP08-KIT")
      (libsource (lib "eagle-import") (part "THAT151X"))
    )
    (comp (ref "J101")
      (value "M031X03_NO_SILK")
      (footprint "eagle-import:1X03_NO_SILK@1")
      (libsource (lib "eagle-import") (part "M031X03_NO_SILK"))
    )
    (comp (ref "J102")
      (value "M031X03_NO_SILK")
      (footprint "eagle-import:1X03_NO_SILK@1")
      (libsource (lib "eagle-import") (part "M031X03_NO_SILK"))
    )
    (comp (ref "J103")
      (value "phantom")
      (footprint "eagle-import:1X01NS-KIT")
      (libsource (lib "eagle-import") (part "M01NOSILK-KIT"))
    )
    (comp (ref "J104")
      (value "eqout")
      (footprint "eagle-import:1X01NS-KIT")
      (libsource (lib "eagle-import") (part "M01NOSILK-KIT"))
    )
    (comp (ref "J105")
      (value "eqout")
      (footprint "eagle-import:1X01NS-KIT")
      (libsource (lib "eagle-import") (part "M01NOSILK-KIT"))
    )
    (comp (ref "J106")
      (value "CONN_05PTH_LONGPADS")
      (footprint "eagle-import:1X05_LONGPADS")
      (libsource (lib "eagle-import") (part "CONN_05PTH_LONGPADS"))
    )
    (comp (ref "R101")
      (value "6k8")
      (footprint "eagle-import:AXIAL-0.3")
      (libsource (lib "eagle-import") (part "RESISTOR"))
    )
    (comp (ref "R102")
      (value "6k8")
      (footprint "eagle-import:AXIAL-0.3")
      (libsource (lib "eagle-import") (part "RESISTOR"))
    )
    (comp (ref "R103")
      (value "10")
      (footprint "eagle-import:AXIAL-0.3")
      (libsource (lib "eagle-import") (part "RESISTOR"))
    )
    (comp (ref "R104")
      (value "10")
      (footprint "eagle-import:AXIAL-0.3")
      (libsource (lib "eagle-import") (part "RESISTOR"))
    )
    (comp (ref "R105")
      (value "4k99")
      (footprint "eagle-import:AXIAL-0.3")
      (libsource (lib "eagle-import") (part "RESISTOR"))
    )
    (comp (ref "R106")
      (value "4k99")
      (footprint "eagle-import:AXIAL-0.3")
      (libsource (lib "eagle-import") (part "RESISTOR"))
    )
    (comp (ref "R107")
      (value "22k")
      (footprint "eagle-import:AXIAL-0.3")
      (libsource (lib "eagle-import") (part "RESISTOR"))
    )
    (comp (ref "R108")
      (value "1k2")
      (footprint "eagle-import:AXIAL-0.3")
      (libsource (lib "eagle-import") (part "RESISTOR"))
    )
    (comp (ref "R109")
      (value "1k2")
      (footprint "eagle-import:AXIAL-0.3")
      (libsource (lib "eagle-import") (part "RESISTOR"))
    )
    (comp (ref "R110")
      (value "5")
      (footprint "eagle-import:AXIAL-0.3")
      (libsource (lib "eagle-import") (part "RESISTOR"))
    )
    (comp (ref "R111")
      (value "1k8")
      (footprint "eagle-import:AXIAL-0.3")
      (libsource (lib "eagle-import") (part "RESISTOR"))
    )
    (comp (ref "R112")
      (value "1k8")
      (footprint "eagle-import:AXIAL-0.3")
      (libsource (lib "eagle-import") (part "RESISTOR"))
    )
    (comp (ref "R113")
      (value "12k")
      (footprint "eagle-import:AXIAL-0.3")
      (libsource (lib "eagle-import") (part "RESISTOR"))
    )
    (comp (ref "R114")
      (value "1k")
      (footprint "eagle-import:AXIAL-0.3")
      (libsource (lib "eagle-import") (part "RESISTOR"))
    )
    (comp (ref "R115")
      (value "1k")
      (footprint "eagle-import:AXIAL-0.3")
      (libsource (lib "eagle-import") (part "RESISTOR"))
    )
    (comp (ref "R116")
      (value "1k")
      (footprint "eagle-import:AXIAL-0.3")
      (libsource (lib "eagle-import") (part "RESISTOR"))
    )
    (comp (ref "U101")
      (value "lme49710")
      (footprint "eagle-import:DIP08-KIT")
      (libsource (lib "eagle-import") (part "OPAMPLME49710"))
    )
    (comp (ref "VR101")
      (value "10K")
      (footprint "eagle-import:ROT-SW-POT")
      (libsource (lib "eagle-import") (part "POTROT-SW-POT"))
    )
    (comp (ref "VR102")
      (value "10K")
      (footprint "eagle-import:ALPHA-RV24AF40-POT")
      (libsource (lib "eagle-import") (part "POT10K-VERTPIN"))
    )
    (comp (ref "VR103")
      (value "10K")
      (footprint "eagle-import:ALPHA-RV24AF40-POT")
      (libsource (lib "eagle-import") (part "POT10K-VERTPIN"))
    )
    (comp (ref "C701")
      (value "1000u/35V")
      (footprint "eagle-import:CAP-PANA-5LS-12.5DIAM")
      (libsource (lib "eagle-import") (part "CAP-LYTIC1000U/35V"))
    )
    (comp (ref "C702")
      (value "1000u/35V")
      (footprint "eagle-import:CAP-PANA-5LS-12.5DIAM")
      (libsource (lib "eagle-import") (part "CAP-LYTIC1000U/35V"))
    )
    (comp (ref "D701")
      (value "LED5MM")
      (footprint "eagle-import:LED_5MM")
      (libsource (lib "eagle-import") (part "LED5MM"))
    )
    (comp (ref "FRAME701")
      (value "FRAME-LEDGER")
      (footprint "eagle-import:CREATIVE_COMMONS")
      (libsource (lib "eagle-import") (part "FRAME-LEDGER"))
    )
    (comp (ref "J701")
      (value "power")
      (footprint "eagle-import:MOLEX-1X3_LOCK")
      (libsource (lib "eagle-import") (part "CONN_03POLAR_LOCK"))
    )
    (comp (ref "R701")
      (value "10")
      (footprint "eagle-import:AXIAL-0.3")
      (libsource (lib "eagle-import") (part "RESISTORAXIAL-0.3"))
    )
    (comp (ref "R702")
      (value "10")
      (footprint "eagle-import:AXIAL-0.3")
      (libsource (lib "eagle-import") (part "RESISTORAXIAL-0.3"))
    )
    (comp (ref "R703")
      (value "1k5")
      (footprint "eagle-import:AXIAL-0.3")
      (libsource (lib "eagle-import") (part "RESISTORAXIAL-0.3"))
    )
    (comp (ref "C1")
      (value "0.01uf")
      (footprint "eagle-import:WIMA-MKS2-2.5X7.2")
      (libsource (lib "eagle-import") (part "WIMA-MKS20.01UF"))
    )
    (comp (ref "C2")
      (value "0.01uf")
      (footprint "eagle-import:WIMA-MKS2-2.5X7.2")
      (libsource (lib "eagle-import") (part "WIMA-MKS20.01UF"))
    )
    (comp (ref "C5")
      (value "1uf/160V")
      (footprint "eagle-import:CAP-PANA-2.5LS-6DIAM")
      (libsource (lib "eagle-import") (part "CAP-LYTIC1UF/160V"))
    )
    (comp (ref "C6")
      (value "1uf/160V")
      (footprint "eagle-import:CAP-PANA-2.5LS-6DIAM")
      (libsource (lib "eagle-import") (part "CAP-LYTIC1UF/160V"))
    )
    (comp (ref "C601")
      (value "100pf")
      (footprint "eagle-import:CAP-KEMET-GM-2.54LS")
      (libsource (lib "eagle-import") (part "CAP-CERAMIC100PF"))
    )
    (comp (ref "C602")
      (value "47u/25V")
      (footprint "eagle-import:CAP-PANA-2LS-5DIAM")
      (libsource (lib "eagle-import") (part "CAP-LYTIC47U/25V"))
    )
    (comp (ref "C603")
      (value "0.01uf")
      (footprint "eagle-import:WIMA-MKS2-2.5X7.2")
      (libsource (lib "eagle-import") (part "WIMA-MKS20.01UF"))
    )
    (comp (ref "C604")
      (value "0.01uf")
      (footprint "eagle-import:WIMA-MKS2-2.5X7.2")
      (libsource (lib "eagle-import") (part "WIMA-MKS20.01UF"))
    )
    (comp (ref "C605")
      (value "100pf")
      (footprint "eagle-import:CAP-KEMET-GM-2.54LS")
      (libsource (lib "eagle-import") (part "CAP-CERAMIC100PF"))
    )
    (comp (ref "D1")
      (value "1n4148")
      (footprint "eagle-import:DIODE-1N4148")
      (libsource (lib "eagle-import") (part "DIODE-1N4148"))
    )
    (comp (ref "D2")
      (value "1n4148")
      (footprint "eagle-import:DIODE-1N4148")
      (libsource (lib "eagle-import") (part "DIODE-1N4148"))
    )
    (comp (ref "D601")
      (value "RECTIFIERRB15X")
      (footprint "eagle-import:SM-RECTIFIER")
      (libsource (lib "eagle-import") (part "RECTIFIERRB15X"))
    )
    (comp (ref "D602")
      (value "RED")
      (footprint "eagle-import:LED_BARGRAPH_10")
      (libsource (lib "eagle-import") (part "LED_BARGRAPH_10RED"))
    )
    (comp (ref "FB601")
      (value "FB")
      (footprint "eagle-import:BEAD")
      (libsource (lib "eagle-import") (part "FB"))
    )
    (comp (ref "FRAME601")
      (value "FRAME-LEDGER")
      (footprint "eagle-import:CREATIVE_COMMONS")
      (libsource (lib "eagle-import") (part "FRAME-LEDGER"))
    )
    (comp (ref "H601")
      (value "STAND-OFF")
      (footprint "eagle-import:STAND-OFF")
      (libsource (lib "eagle-import") (part "STAND-OFF"))
    )
    (comp (ref "H602")
      (value "STAND-OFF")
      (footprint "eagle-import:STAND-OFF")
      (libsource (lib "eagle-import") (part "STAND-OFF"))
    )
    (comp (ref "H603")
      (value "STAND-OFF")
      (footprint "eagle-import:STAND-OFF")
      (libsource (lib "eagle-import") (part "STAND-OFF"))
    )
    (comp (ref "H605")
      (value "STAND-OFF")
      (footprint "eagle-import:STAND-OFF")
      (libsource (lib "eagle-import") (part "STAND-OFF"))
    )
    (comp (ref "H612")
      (value "STAND-OFF")
      (footprint "eagle-import:STAND-OFF")
      (libsource (lib "eagle-import") (part "STAND-OFF"))
    )
    (comp (ref "J601")
      (value "out2")
      (footprint "eagle-import:1X02_LOCK_LONGPADS")
      (libsource (lib "eagle-import") (part "CONN_02LOCK_LONGPADS"))
    )
    (comp (ref "R1")
      (value "10k")
      (footprint "eagle-import:AXIAL-0.3")
      (libsource (lib "eagle-import") (part "RESISTOR"))
    )
    (comp (ref "R2")
      (value "100k")
      (footprint "eagle-import:AXIAL-0.3")
      (libsource (lib "eagle-import") (part "RESISTOR"))
    )
    (comp (ref "R3")
      (value "1k")
      (footprint "eagle-import:AXIAL-0.3")
      (libsource (lib "eagle-import") (part "RESISTOR"))
    )
    (comp (ref "R601")
      (value "10k")
      (footprint "eagle-import:AXIAL-0.3")
      (libsource (lib "eagle-import") (part "RESISTOR"))
    )
    (comp (ref "R602")
      (value "10k")
      (footprint "eagle-import:AXIAL-0.3")
      (libsource (lib "eagle-import") (part "RESISTOR"))
    )
    (comp (ref "R603")
      (value "10k")
      (footprint "eagle-import:AXIAL-0.3")
      (libsource (lib "eagle-import") (part "RESISTOR"))
    )
    (comp (ref "R604")
      (value "10k")
      (footprint "eagle-import:AXIAL-0.3")
      (libsource (lib "eagle-import") (part "RESISTOR"))
    )
    (comp (ref "R605")
      (value "10k")
      (footprint "eagle-import:AXIAL-0.3")
      (libsource (lib "eagle-import") (part "RESISTOR"))
    )
    (comp (ref "R606")
      (value "10k")
      (footprint "eagle-import:AXIAL-0.3")
      (libsource (lib "eagle-import") (part "RESISTOR"))
    )
    (comp (ref "R607")
      (value "100")
      (footprint "eagle-import:AXIAL-0.3")
      (libsource (lib "eagle-import") (part "RESISTOR"))
    )
    (comp (ref "R608")
      (value "47k")
      (footprint "eagle-import:AXIAL-0.3")
      (libsource (lib "eagle-import") (part "RESISTOR"))
    )
    (comp (ref "R609")
      (value "???")
      (footprint "eagle-import:AXIAL-0.3")
      (libsource (lib "eagle-import") (part "RESISTOR"))
    )
    (comp (ref "R610")
      (value "???")
      (footprint "eagle-import:AXIAL-0.3")
      (libsource (lib "eagle-import") (part "RESISTOR"))
    )
    (comp (ref "R611")
      (value "???")
      (footprint "eagle-import:AXIAL-0.3")
      (libsource (lib "eagle-import") (part "RESISTOR"))
    )
    (comp (ref "U1")
      (value "LM358")
      (footprint "eagle-import:DIP08")
      (libsource (lib "eagle-import") (part "LM358"))
    )
    (comp (ref "U601")
      (value "lme49710")
      (footprint "eagle-import:DIP08-KIT")
      (libsource (lib "eagle-import") (part "OPAMPLME49710"))
    )
    (comp (ref "U602")
      (value "LM3915N")
      (footprint "eagle-import:DIL18")
      (libsource (lib "eagle-import") (part "LM391N5"))
    )
    (comp (ref "C3")
      (value "1uf/160V")
      (footprint "eagle-import:CAP-PANA-2.5LS-6DIAM")
      (libsource (lib "eagle-import") (part "CAP-LYTIC1UF/160V"))
    )
    (comp (ref "C4")
      (value "1uf/160V")
      (footprint "eagle-import:CAP-PANA-2.5LS-6DIAM")
      (libsource (lib "eagle-import") (part "CAP-LYTIC1UF/160V"))
    )
    (comp (ref "C501")
      (value "100pf")
      (footprint "eagle-import:CAP-KEMET-GM-2.54LS")
      (libsource (lib "eagle-import") (part "CAP-CERAMIC100PF"))
    )
    (comp (ref "C502")
      (value "47u/25V")
      (footprint "eagle-import:CAP-PANA-2LS-5DIAM")
      (libsource (lib "eagle-import") (part "CAP-LYTIC47U/25V"))
    )
    (comp (ref "C503")
      (value "0.01uf")
      (footprint "eagle-import:WIMA-MKS2-2.5X7.2")
      (libsource (lib "eagle-import") (part "WIMA-MKS20.01UF"))
    )
    (comp (ref "C504")
      (value "0.01uf")
      (footprint "eagle-import:WIMA-MKS2-2.5X7.2")
      (libsource (lib "eagle-import") (part "WIMA-MKS20.01UF"))
    )
    (comp (ref "C505")
      (value "100pf")
      (footprint "eagle-import:CAP-KEMET-GM-2.54LS")
      (libsource (lib "eagle-import") (part "CAP-CERAMIC100PF"))
    )
    (comp (ref "D3")
      (value "1n4148")
      (footprint "eagle-import:DIODE-1N4148")
      (libsource (lib "eagle-import") (part "DIODE-1N4148"))
    )
    (comp (ref "D4")
      (value "1n4148")
      (footprint "eagle-import:DIODE-1N4148")
      (libsource (lib "eagle-import") (part "DIODE-1N4148"))
    )
    (comp (ref "D501")
      (value "RECTIFIERRB15X")
      (footprint "eagle-import:SM-RECTIFIER")
      (libsource (lib "eagle-import") (part "RECTIFIERRB15X"))
    )
    (comp (ref "D502")
      (value "RED")
      (footprint "eagle-import:LED_BARGRAPH_10")
      (libsource (lib "eagle-import") (part "LED_BARGRAPH_10RED"))
    )
    (comp (ref "FB501")
      (value "FB")
      (footprint "eagle-import:BEAD")
      (libsource (lib "eagle-import") (part "FB"))
    )
    (comp (ref "FRAME501")
      (value "FRAME-LEDGER")
      (footprint "eagle-import:CREATIVE_COMMONS")
      (libsource (lib "eagle-import") (part "FRAME-LEDGER"))
    )
    (comp (ref "J501")
      (value "out2")
      (footprint "eagle-import:1X02_LOCK_LONGPADS")
      (libsource (lib "eagle-import") (part "CONN_02LOCK_LONGPADS"))
    )
    (comp (ref "R4")
      (value "10k")
      (footprint "eagle-import:AXIAL-0.3")
      (libsource (lib "eagle-import") (part "RESISTOR"))
    )
    (comp (ref "R5")
      (value "100k")
      (footprint "eagle-import:AXIAL-0.3")
      (libsource (lib "eagle-import") (part "RESISTOR"))
    )
    (comp (ref "R6")
      (value "1k")
      (footprint "eagle-import:AXIAL-0.3")
      (libsource (lib "eagle-import") (part "RESISTOR"))
    )
    (comp (ref "R501")
      (value "10k")
      (footprint "eagle-import:AXIAL-0.3")
      (libsource (lib "eagle-import") (part "RESISTOR"))
    )
    (comp (ref "R502")
      (value "10k")
      (footprint "eagle-import:AXIAL-0.3")
      (libsource (lib "eagle-import") (part "RESISTOR"))
    )
    (comp (ref "R503")
      (value "10k")
      (footprint "eagle-import:AXIAL-0.3")
      (libsource (lib "eagle-import") (part "RESISTOR"))
    )
    (comp (ref "R504")
      (value "10k")
      (footprint "eagle-import:AXIAL-0.3")
      (libsource (lib "eagle-import") (part "RESISTOR"))
    )
    (comp (ref "R505")
      (value "10k")
      (footprint "eagle-import:AXIAL-0.3")
      (libsource (lib "eagle-import") (part "RESISTOR"))
    )
    (comp (ref "R506")
      (value "10k")
      (footprint "eagle-import:AXIAL-0.3")
      (libsource (lib "eagle-import") (part "RESISTOR"))
    )
    (comp (ref "R507")
      (value "100")
      (footprint "eagle-import:AXIAL-0.3")
      (libsource (lib "eagle-import") (part "RESISTOR"))
    )
    (comp (ref "R508")
      (value "47k")
      (footprint "eagle-import:AXIAL-0.3")
      (libsource (lib "eagle-import") (part "RESISTOR"))
    )
    (comp (ref "R509")
      (value "???")
      (footprint "eagle-import:AXIAL-0.3")
      (libsource (lib "eagle-import") (part "RESISTOR"))
    )
    (comp (ref "R510")
      (value "???")
      (footprint "eagle-import:AXIAL-0.3")
      (libsource (lib "eagle-import") (part "RESISTOR"))
    )
    (comp (ref "R511")
      (value "???")
      (footprint "eagle-import:AXIAL-0.3")
      (libsource (lib "eagle-import") (part "RESISTOR"))
    )
    (comp (ref "U501")
      (value "lme49710")
      (footprint "eagle-import:DIP08-KIT")
      (libsource (lib "eagle-import") (part "OPAMPLME49710"))
    )
    (comp (ref "U502")
      (value "LM3915N")
      (footprint "eagle-import:DIL18")
      (libsource (lib "eagle-import") (part "LM391N5"))
    )
    (comp (ref "C401")
      (value "47pf")
      (footprint "eagle-import:CAP-KEMET-GM-2.54LS")
      (libsource (lib "eagle-import") (part "CAP-CERAMIC47PF"))
    )
    (comp (ref "C402")
      (value "47pf")
      (footprint "eagle-import:CAP-KEMET-GM-2.54LS")
      (libsource (lib "eagle-import") (part "CAP-CERAMIC47PF"))
    )
    (comp (ref "C403")
      (value "470pf")
      (footprint "eagle-import:CAP-KEMET-GM-2.54LS")
      (libsource (lib "eagle-import") (part "CAP-CERAMIC470PF"))
    )
    (comp (ref "C404")
      (value "470pf")
      (footprint "eagle-import:CAP-KEMET-GM-2.54LS")
      (libsource (lib "eagle-import") (part "CAP-CERAMIC470PF"))
    )
    (comp (ref "C405")
      (value "470pf")
      (footprint "eagle-import:CAP-KEMET-GM-2.54LS")
      (libsource (lib "eagle-import") (part "CAP-CERAMIC470PF"))
    )
    (comp (ref "C406")
      (value "470pf")
      (footprint "eagle-import:CAP-KEMET-GM-2.54LS")
      (libsource (lib "eagle-import") (part "CAP-CERAMIC470PF"))
    )
    (comp (ref "C407")
      (value "47u/63V")
      (footprint "eagle-import:CAP-PANA-2LS-6DIAM")
      (libsource (lib "eagle-import") (part "CAP-LYTIC47U/63V"))
    )
    (comp (ref "C408")
      (value "47u/63V")
      (footprint "eagle-import:CAP-PANA-2LS-6DIAM")
      (libsource (lib "eagle-import") (part "CAP-LYTIC47U/63V"))
    )
    (comp (ref "C409")
      (value "47u/25V")
      (footprint "eagle-import:CAP-PANA-2LS-5DIAM")
      (libsource (lib "eagle-import") (part "CAP-LYTIC47U/25V"))
    )
    (comp (ref "C410")
      (value "47u/25V")
      (footprint "eagle-import:CAP-PANA-2LS-5DIAM")
      (libsource (lib "eagle-import") (part "CAP-LYTIC47U/25V"))
    )
    (comp (ref "C411")
      (value "6800u/25V")
      (footprint "eagle-import:CAP-PANA-5LS-12.5DIAM")
      (libsource (lib "eagle-import") (part "CAP-LYTIC6800U/10V"))
    )
    (comp (ref "C412")
      (value "470pf")
      (footprint "eagle-import:CAP-KEMET-GM-2.54LS")
      (libsource (lib "eagle-import") (part "CAP-CERAMIC470PF"))
    )
    (comp (ref "C413")
      (value "470pf")
      (footprint "eagle-import:CAP-KEMET-GM-2.54LS")
      (libsource (lib "eagle-import") (part "CAP-CERAMIC470PF"))
    )
    (comp (ref "C414")
      (value "47u/25V")
      (footprint "eagle-import:CAP-PANA-2LS-5DIAM")
      (libsource (lib "eagle-import") (part "CAP-LYTIC47U/25V"))
    )
    (comp (ref "C415")
      (value "0.1uf")
      (footprint "eagle-import:WIMA-MKS2-2.5X7.2")
      (libsource (lib "eagle-import") (part "WIMA-MKS20.1UF"))
    )
    (comp (ref "C416")
      (value "0.1uf")
      (footprint "eagle-import:WIMA-MKS2-2.5X7.2")
      (libsource (lib "eagle-import") (part "WIMA-MKS20.1UF"))
    )
    (comp (ref "C417")
      (value "0.015uf")
      (footprint "eagle-import:WIMA-MKS2-2.5X7.2")
      (libsource (lib "eagle-import") (part "WIMA-MKS20.015UF"))
    )
    (comp (ref "C418")
      (value "0.015uf")
      (footprint "eagle-import:WIMA-MKS2-2.5X7.2")
      (libsource (lib "eagle-import") (part "WIMA-MKS20.015UF"))
    )
    (comp (ref "C419")
      (value "100pf")
      (footprint "eagle-import:CAP-KEMET-GM-2.54LS")
      (libsource (lib "eagle-import") (part "CAP-CERAMIC100PF"))
    )
    (comp (ref "C420")
      (value "47u/25V")
      (footprint "eagle-import:CAP-PANA-2LS-5DIAM")
      (libsource (lib "eagle-import") (part "CAP-LYTIC47U/25V"))
    )
    (comp (ref "C421")
      (value "0.01uf")
      (footprint "eagle-import:WIMA-MKS2-2.5X7.2")
      (libsource (lib "eagle-import") (part "WIMA-MKS20.01UF"))
    )
    (comp (ref "C422")
      (value "0.01uf")
      (footprint "eagle-import:WIMA-MKS2-2.5X7.2")
      (libsource (lib "eagle-import") (part "WIMA-MKS20.01UF"))
    )
    (comp (ref "D401")
      (value "RECTIFIERRB15X")
      (footprint "eagle-import:SM-RECTIFIER")
      (libsource (lib "eagle-import") (part "RECTIFIERRB15X"))
    )
    (comp (ref "D402")
      (value "200mA/100V/1V")
      (footprint "eagle-import:DIODE-1N4148")
      (libsource (lib "eagle-import") (part "DIODE-1N4148"))
    )
    (comp (ref "D403")
      (value "200mA/100V/1V")
      (footprint "eagle-import:DIODE-1N4148")
      (libsource (lib "eagle-import") (part "DIODE-1N4148"))
    )
    (comp (ref "FRAME401")
      (value "FRAME-LEDGER")
      (footprint "eagle-import:CREATIVE_COMMONS")
      (libsource (lib "eagle-import") (part "FRAME-LEDGER"))
    )
    (comp (ref "IC401")
      (value "THAT1512")
      (footprint "eagle-import:DIP08-KIT")
      (libsource (lib "eagle-import") (part "THAT151X"))
    )
    (comp (ref "J401")
      (value "M031X03_NO_SILK")
      (footprint "eagle-import:1X03_NO_SILK@1")
      (libsource (lib "eagle-import") (part "M031X03_NO_SILK"))
    )
    (comp (ref "J402")
      (value "M031X03_NO_SILK")
      (footprint "eagle-import:1X03_NO_SILK@1")
      (libsource (lib "eagle-import") (part "M031X03_NO_SILK"))
    )
    (comp (ref "J403")
      (value "phantom")
      (footprint "eagle-import:1X01NS-KIT")
      (libsource (lib "eagle-import") (part "M01NOSILK-KIT"))
    )
    (comp (ref "J404")
      (value "eqout")
      (footprint "eagle-import:1X01NS-KIT")
      (libsource (lib "eagle-import") (part "M01NOSILK-KIT"))
    )
    (comp (ref "J405")
      (value "eqout")
      (footprint "eagle-import:1X01NS-KIT")
      (libsource (lib "eagle-import") (part "M01NOSILK-KIT"))
    )
    (comp (ref "J406")
      (value "CONN_05PTH_LONGPADS")
      (footprint "eagle-import:1X05_LONGPADS")
      (libsource (lib "eagle-import") (part "CONN_05PTH_LONGPADS"))
    )
    (comp (ref "R401")
      (value "6k8")
      (footprint "eagle-import:AXIAL-0.3")
      (libsource (lib "eagle-import") (part "RESISTOR"))
    )
    (comp (ref "R402")
      (value "6k8")
      (footprint "eagle-import:AXIAL-0.3")
      (libsource (lib "eagle-import") (part "RESISTOR"))
    )
    (comp (ref "R403")
      (value "10")
      (footprint "eagle-import:AXIAL-0.3")
      (libsource (lib "eagle-import") (part "RESISTOR"))
    )
    (comp (ref "R404")
      (value "10")
      (footprint "eagle-import:AXIAL-0.3")
      (libsource (lib "eagle-import") (part "RESISTOR"))
    )
    (comp (ref "R405")
      (value "4k99")
      (footprint "eagle-import:AXIAL-0.3")
      (libsource (lib "eagle-import") (part "RESISTOR"))
    )
    (comp (ref "R406")
      (value "4k99")
      (footprint "eagle-import:AXIAL-0.3")
      (libsource (lib "eagle-import") (part "RESISTOR"))
    )
    (comp (ref "R407")
      (value "22k")
      (footprint "eagle-import:AXIAL-0.3")
      (libsource (lib "eagle-import") (part "RESISTOR"))
    )
    (comp (ref "R408")
      (value "1k2")
      (footprint "eagle-import:AXIAL-0.3")
      (libsource (lib "eagle-import") (part "RESISTOR"))
    )
    (comp (ref "R409")
      (value "1k2")
      (footprint "eagle-import:AXIAL-0.3")
      (libsource (lib "eagle-import") (part "RESISTOR"))
    )
    (comp (ref "R410")
      (value "5")
      (footprint "eagle-import:AXIAL-0.3")
      (libsource (lib "eagle-import") (part "RESISTOR"))
    )
    (comp (ref "R411")
      (value "1k8")
      (footprint "eagle-import:AXIAL-0.3")
      (libsource (lib "eagle-import") (part "RESISTOR"))
    )
    (comp (ref "R412")
      (value "1k8")
      (footprint "eagle-import:AXIAL-0.3")
      (libsource (lib "eagle-import") (part "RESISTOR"))
    )
    (comp (ref "R413")
      (value "12k")
      (footprint "eagle-import:AXIAL-0.3")
      (libsource (lib "eagle-import") (part "RESISTOR"))
    )
    (comp (ref "R414")
      (value "1k")
      (footprint "eagle-import:AXIAL-0.3")
      (libsource (lib "eagle-import") (part "RESISTOR"))
    )
    (comp (ref "R415")
      (value "1k")
      (footprint "eagle-import:AXIAL-0.3")
      (libsource (lib "eagle-import") (part "RESISTOR"))
    )
    (comp (ref "R416")
      (value "1k")
      (footprint "eagle-import:AXIAL-0.3")
      (libsource (lib "eagle-import") (part "RESISTOR"))
    )
    (comp (ref "U401")
      (value "lme49710")
      (footprint "eagle-import:DIP08-KIT")
      (libsource (lib "eagle-import") (part "OPAMPLME49710"))
    )
    (comp (ref "VR401")
      (value "10K")
      (footprint "eagle-import:ROT-SW-POT")
      (libsource (lib "eagle-import") (part "POTROT-SW-POT"))
    )
    (comp (ref "VR402")
      (value "10K")
      (footprint "eagle-import:ALPHA-RV24AF40-POT")
      (libsource (lib "eagle-import") (part "POT10K-VERTPIN"))
    )
    (comp (ref "VR403")
      (value "10K")
      (footprint "eagle-import:ALPHA-RV24AF40-POT")
      (libsource (lib "eagle-import") (part "POT10K-VERTPIN"))
    )
    (comp (ref "C201")
      (value "47pf")
      (footprint "eagle-import:CAP-KEMET-GM-2.54LS")
      (libsource (lib "eagle-import") (part "CAP-CERAMIC47PF"))
    )
    (comp (ref "C202")
      (value "47pf")
      (footprint "eagle-import:CAP-KEMET-GM-2.54LS")
      (libsource (lib "eagle-import") (part "CAP-CERAMIC47PF"))
    )
    (comp (ref "C203")
      (value "470pf")
      (footprint "eagle-import:CAP-KEMET-GM-2.54LS")
      (libsource (lib "eagle-import") (part "CAP-CERAMIC470PF"))
    )
    (comp (ref "C204")
      (value "470pf")
      (footprint "eagle-import:CAP-KEMET-GM-2.54LS")
      (libsource (lib "eagle-import") (part "CAP-CERAMIC470PF"))
    )
    (comp (ref "C205")
      (value "470pf")
      (footprint "eagle-import:CAP-KEMET-GM-2.54LS")
      (libsource (lib "eagle-import") (part "CAP-CERAMIC470PF"))
    )
    (comp (ref "C206")
      (value "470pf")
      (footprint "eagle-import:CAP-KEMET-GM-2.54LS")
      (libsource (lib "eagle-import") (part "CAP-CERAMIC470PF"))
    )
    (comp (ref "C207")
      (value "47u/63V")
      (footprint "eagle-import:CAP-PANA-2LS-6DIAM")
      (libsource (lib "eagle-import") (part "CAP-LYTIC47U/63V"))
    )
    (comp (ref "C208")
      (value "47u/63V")
      (footprint "eagle-import:CAP-PANA-2LS-6DIAM")
      (libsource (lib "eagle-import") (part "CAP-LYTIC47U/63V"))
    )
    (comp (ref "C209")
      (value "47u/25V")
      (footprint "eagle-import:CAP-PANA-2LS-5DIAM")
      (libsource (lib "eagle-import") (part "CAP-LYTIC47U/25V"))
    )
    (comp (ref "C210")
      (value "47u/25V")
      (footprint "eagle-import:CAP-PANA-2LS-5DIAM")
      (libsource (lib "eagle-import") (part "CAP-LYTIC47U/25V"))
    )
    (comp (ref "C211")
      (value "6800u/25V")
      (footprint "eagle-import:CAP-PANA-5LS-12.5DIAM")
      (libsource (lib "eagle-import") (part "CAP-LYTIC6800U/10V"))
    )
    (comp (ref "C212")
      (value "470pf")
      (footprint "eagle-import:CAP-KEMET-GM-2.54LS")
      (libsource (lib "eagle-import") (part "CAP-CERAMIC470PF"))
    )
    (comp (ref "C213")
      (value "470pf")
      (footprint "eagle-import:CAP-KEMET-GM-2.54LS")
      (libsource (lib "eagle-import") (part "CAP-CERAMIC470PF"))
    )
    (comp (ref "C214")
      (value "47u/25V")
      (footprint "eagle-import:CAP-PANA-2LS-5DIAM")
      (libsource (lib "eagle-import") (part "CAP-LYTIC47U/25V"))
    )
    (comp (ref "C215")
      (value "0.1uf")
      (footprint "eagle-import:WIMA-MKS2-2.5X7.2")
      (libsource (lib "eagle-import") (part "WIMA-MKS20.1UF"))
    )
    (comp (ref "C216")
      (value "0.1uf")
      (footprint "eagle-import:WIMA-MKS2-2.5X7.2")
      (libsource (lib "eagle-import") (part "WIMA-MKS20.1UF"))
    )
    (comp (ref "C217")
      (value "0.015uf")
      (footprint "eagle-import:WIMA-MKS2-2.5X7.2")
      (libsource (lib "eagle-import") (part "WIMA-MKS20.015UF"))
    )
    (comp (ref "C218")
      (value "0.015uf")
      (footprint "eagle-import:WIMA-MKS2-2.5X7.2")
      (libsource (lib "eagle-import") (part "WIMA-MKS20.015UF"))
    )
    (comp (ref "C219")
      (value "100pf")
      (footprint "eagle-import:CAP-KEMET-GM-2.54LS")
      (libsource (lib "eagle-import") (part "CAP-CERAMIC100PF"))
    )
    (comp (ref "C220")
      (value "47u/25V")
      (footprint "eagle-import:CAP-PANA-2LS-5DIAM")
      (libsource (lib "eagle-import") (part "CAP-LYTIC47U/25V"))
    )
    (comp (ref "C221")
      (value "0.01uf")
      (footprint "eagle-import:WIMA-MKS2-2.5X7.2")
      (libsource (lib "eagle-import") (part "WIMA-MKS20.01UF"))
    )
    (comp (ref "C222")
      (value "0.01uf")
      (footprint "eagle-import:WIMA-MKS2-2.5X7.2")
      (libsource (lib "eagle-import") (part "WIMA-MKS20.01UF"))
    )
    (comp (ref "D201")
      (value "RECTIFIERRB15X")
      (footprint "eagle-import:SM-RECTIFIER")
      (libsource (lib "eagle-import") (part "RECTIFIERRB15X"))
    )
    (comp (ref "D202")
      (value "200mA/100V/1V")
      (footprint "eagle-import:DIODE-1N4148")
      (libsource (lib "eagle-import") (part "DIODE-1N4148"))
    )
    (comp (ref "D203")
      (value "200mA/100V/1V")
      (footprint "eagle-import:DIODE-1N4148")
      (libsource (lib "eagle-import") (part "DIODE-1N4148"))
    )
    (comp (ref "FRAME201")
      (value "FRAME-LEDGER")
      (footprint "eagle-import:CREATIVE_COMMONS")
      (libsource (lib "eagle-import") (part "FRAME-LEDGER"))
    )
    (comp (ref "IC201")
      (value "THAT1512")
      (footprint "eagle-import:DIP08-KIT")
      (libsource (lib "eagle-import") (part "THAT151X"))
    )
    (comp (ref "J201")
      (value "M031X03_NO_SILK")
      (footprint "eagle-import:1X03_NO_SILK@1")
      (libsource (lib "eagle-import") (part "M031X03_NO_SILK"))
    )
    (comp (ref "J202")
      (value "M031X03_NO_SILK")
      (footprint "eagle-import:1X03_NO_SILK@1")
      (libsource (lib "eagle-import") (part "M031X03_NO_SILK"))
    )
    (comp (ref "J203")
      (value "phantom")
      (footprint "eagle-import:1X01NS-KIT")
      (libsource (lib "eagle-import") (part "M01NOSILK-KIT"))
    )
    (comp (ref "J204")
      (value "eqout")
      (footprint "eagle-import:1X01NS-KIT")
      (libsource (lib "eagle-import") (part "M01NOSILK-KIT"))
    )
    (comp (ref "J205")
      (value "eqout")
      (footprint "eagle-import:1X01NS-KIT")
      (libsource (lib "eagle-import") (part "M01NOSILK-KIT"))
    )
    (comp (ref "J206")
      (value "CONN_05PTH_LONGPADS")
      (footprint "eagle-import:1X05_LONGPADS")
      (libsource (lib "eagle-import") (part "CONN_05PTH_LONGPADS"))
    )
    (comp (ref "R201")
      (value "6k8")
      (footprint "eagle-import:AXIAL-0.3")
      (libsource (lib "eagle-import") (part "RESISTOR"))
    )
    (comp (ref "R202")
      (value "6k8")
      (footprint "eagle-import:AXIAL-0.3")
      (libsource (lib "eagle-import") (part "RESISTOR"))
    )
    (comp (ref "R203")
      (value "10")
      (footprint "eagle-import:AXIAL-0.3")
      (libsource (lib "eagle-import") (part "RESISTOR"))
    )
    (comp (ref "R204")
      (value "10")
      (footprint "eagle-import:AXIAL-0.3")
      (libsource (lib "eagle-import") (part "RESISTOR"))
    )
    (comp (ref "R205")
      (value "4k99")
      (footprint "eagle-import:AXIAL-0.3")
      (libsource (lib "eagle-import") (part "RESISTOR"))
    )
    (comp (ref "R206")
      (value "4k99")
      (footprint "eagle-import:AXIAL-0.3")
      (libsource (lib "eagle-import") (part "RESISTOR"))
    )
    (comp (ref "R207")
      (value "22k")
      (footprint "eagle-import:AXIAL-0.3")
      (libsource (lib "eagle-import") (part "RESISTOR"))
    )
    (comp (ref "R208")
      (value "1k2")
      (footprint "eagle-import:AXIAL-0.3")
      (libsource (lib "eagle-import") (part "RESISTOR"))
    )
    (comp (ref "R209")
      (value "1k2")
      (footprint "eagle-import:AXIAL-0.3")
      (libsource (lib "eagle-import") (part "RESISTOR"))
    )
    (comp (ref "R210")
      (value "5")
      (footprint "eagle-import:AXIAL-0.3")
      (libsource (lib "eagle-import") (part "RESISTOR"))
    )
    (comp (ref "R211")
      (value "1k8")
      (footprint "eagle-import:AXIAL-0.3")
      (libsource (lib "eagle-import") (part "RESISTOR"))
    )
    (comp (ref "R212")
      (value "1k8")
      (footprint "eagle-import:AXIAL-0.3")
      (libsource (lib "eagle-import") (part "RESISTOR"))
    )
    (comp (ref "R213")
      (value "12k")
      (footprint "eagle-import:AXIAL-0.3")
      (libsource (lib "eagle-import") (part "RESISTOR"))
    )
    (comp (ref "R214")
      (value "1k")
      (footprint "eagle-import:AXIAL-0.3")
      (libsource (lib "eagle-import") (part "RESISTOR"))
    )
    (comp (ref "R215")
      (value "1k")
      (footprint "eagle-import:AXIAL-0.3")
      (libsource (lib "eagle-import") (part "RESISTOR"))
    )
    (comp (ref "R216")
      (value "1k")
      (footprint "eagle-import:AXIAL-0.3")
      (libsource (lib "eagle-import") (part "RESISTOR"))
    )
    (comp (ref "U201")
      (value "lme49710")
      (footprint "eagle-import:DIP08-KIT")
      (libsource (lib "eagle-import") (part "OPAMPLME49710"))
    )
    (comp (ref "VR201")
      (value "10K")
      (footprint "eagle-import:ROT-SW-POT")
      (libsource (lib "eagle-import") (part "POTROT-SW-POT"))
    )
    (comp (ref "VR202")
      (value "10K")
      (footprint "eagle-import:ALPHA-RV24AF40-POT")
      (libsource (lib "eagle-import") (part "POT10K-VERTPIN"))
    )
    (comp (ref "VR203")
      (value "10K")
      (footprint "eagle-import:ALPHA-RV24AF40-POT")
      (libsource (lib "eagle-import") (part "POT10K-VERTPIN"))
    )
  )
  (nets
    (net (code "1") (name "1TO1") (class "Default")
      (node (ref "J106") (pin "2") (pinfunction "2_2") (pintype "passive"))
      (node (ref "R501") (pin "P$2") (pinfunction "2_P$2") (pintype "passive"))
    )
    (net (code "2") (name "1TO2") (class "Default")
      (node (ref "J106") (pin "3") (pinfunction "3_3") (pintype "passive"))
      (node (ref "R601") (pin "P$2") (pinfunction "2_P$2") (pintype "passive"))
    )
    (net (code "3") (name "2TO1") (class "Default")
      (node (ref "J206") (pin "2") (pinfunction "2_2") (pintype "passive"))
      (node (ref "R502") (pin "P$2") (pinfunction "2_P$2") (pintype "passive"))
    )
    (net (code "4") (name "2TO2") (class "Default")
      (node (ref "J206") (pin "3") (pinfunction "3_3") (pintype "passive"))
      (node (ref "R602") (pin "P$2") (pinfunction "2_P$2") (pintype "passive"))
    )
    (net (code "5") (name "3TO1") (class "Default")
      (node (ref "J306") (pin "2") (pinfunction "2_2") (pintype "passive"))
      (node (ref "R503") (pin "P$2") (pinfunction "2_P$2") (pintype "passive"))
    )
    (net (code "6") (name "3TO2") (class "Default")
      (node (ref "J306") (pin "3") (pinfunction "3_3") (pintype "passive"))
      (node (ref "R603") (pin "P$2") (pinfunction "2_P$2") (pintype "passive"))
    )
    (net (code "7") (name "4TO1") (class "Default")
      (node (ref "J406") (pin "2") (pinfunction "2_2") (pintype "passive"))
      (node (ref "R504") (pin "P$2") (pinfunction "2_P$2") (pintype "passive"))
    )
    (net (code "8") (name "4TO2") (class "Default")
      (node (ref "J406") (pin "3") (pinfunction "3_3") (pintype "passive"))
      (node (ref "R604") (pin "P$2") (pinfunction "2_P$2") (pintype "passive"))
    )
    (net (code "9") (name "GND") (class "Default")
      (node (ref "C1") (pin "P$1") (pinfunction "1_P$1") (pintype "passive"))
      (node (ref "C112") (pin "P$2") (pinfunction "2_P$2") (pintype "passive"))
      (node (ref "C113") (pin "P$2") (pinfunction "2_P$2") (pintype "passive"))
      (node (ref "C121") (pin "P$2") (pinfunction "2_P$2") (pintype "passive"))
      (node (ref "C122") (pin "P$1") (pinfunction "1_P$1") (pintype "passive"))
      (node (ref "C2") (pin "P$2") (pinfunction "2_P$2") (pintype "passive"))
      (node (ref "C212") (pin "P$2") (pinfunction "2_P$2") (pintype "passive"))
      (node (ref "C213") (pin "P$2") (pinfunction "2_P$2") (pintype "passive"))
      (node (ref "C221") (pin "P$2") (pinfunction "2_P$2") (pintype "passive"))
      (node (ref "C222") (pin "P$1") (pinfunction "1_P$1") (pintype "passive"))
      (node (ref "C312") (pin "P$2") (pinfunction "2_P$2") (pintype "passive"))
      (node (ref "C313") (pin "P$2") (pinfunction "2_P$2") (pintype "passive"))
      (node (ref "C321") (pin "P$2") (pinfunction "2_P$2") (pintype "passive"))
      (node (ref "C322") (pin "P$1") (pinfunction "1_P$1") (pintype "passive"))
      (node (ref "C4") (pin "NEG") (pinfunction "-_NEG") (pintype "passive"))
      (node (ref "C412") (pin "P$2") (pinfunction "2_P$2") (pintype "passive"))
      (node (ref "C413") (pin "P$2") (pinfunction "2_P$2") (pintype "passive"))
      (node (ref "C421") (pin "P$2") (pinfunction "2_P$2") (pintype "passive"))
      (node (ref "C422") (pin "P$1") (pinfunction "1_P$1") (pintype "passive"))
      (node (ref "C503") (pin "P$2") (pinfunction "2_P$2") (pintype "passive"))
      (node (ref "C504") (pin "P$1") (pinfunction "1_P$1") (pintype "passive"))
      (node (ref "C505") (pin "P$2") (pinfunction "2_P$2") (pintype "passive"))
      (node (ref "C6") (pin "NEG") (pinfunction "-_NEG") (pintype "passive"))
      (node (ref "C603") (pin "P$2") (pinfunction "2_P$2") (pintype "passive"))
      (node (ref "C604") (pin "P$1") (pinfunction "1_P$1") (pintype "passive"))
      (node (ref "C605") (pin "P$2") (pinfunction "2_P$2") (pintype "passive"))
      (node (ref "C701") (pin "NEG") (pinfunction "-_NEG") (pintype "passive"))
      (node (ref "C702") (pin "POS") (pinfunction "+_POS") (pintype "passive"))
      (node (ref "D701") (pin "K") (pinfunction "C_K") (pintype "passive"))
      (node (ref "IC101") (pin "5") (pinfunction "REF_5") (pintype "bidirectional"))
      (node (ref "IC201") (pin "5") (pinfunction "REF_5") (pintype "bidirectional"))
      (node (ref "IC301") (pin "5") (pinfunction "REF_5") (pintype "bidirectional"))
      (node (ref "IC401") (pin "5") (pinfunction "REF_5") (pintype "bidirectional"))
      (node (ref "J106") (pin "4") (pinfunction "4_4") (pintype "passive"))
      (node (ref "J106") (pin "5") (pinfunction "5_5") (pintype "passive"))
      (node (ref "J206") (pin "4") (pinfunction "4_4") (pintype "passive"))
      (node (ref "J206") (pin "5") (pinfunction "5_5") (pintype "passive"))
      (node (ref "J306") (pin "4") (pinfunction "4_4") (pintype "passive"))
      (node (ref "J306") (pin "5") (pinfunction "5_5") (pintype "passive"))
      (node (ref "J406") (pin "4") (pinfunction "4_4") (pintype "passive"))
      (node (ref "J406") (pin "5") (pinfunction "5_5") (pintype "passive"))
      (node (ref "J501") (pin "2") (pinfunction "2_2") (pintype "passive"))
      (node (ref "J601") (pin "2") (pinfunction "2_2") (pintype "passive"))
      (node (ref "J701") (pin "2") (pinfunction "2_2") (pintype "passive"))
      (node (ref "R107") (pin "P$2") (pinfunction "2_P$2") (pintype "passive"))
      (node (ref "R207") (pin "P$2") (pinfunction "2_P$2") (pintype "passive"))
      (node (ref "R307") (pin "P$2") (pinfunction "2_P$2") (pintype "passive"))
      (node (ref "R407") (pin "P$2") (pinfunction "2_P$2") (pintype "passive"))
      (node (ref "R505") (pin "P$1") (pinfunction "1_P$1") (pintype "passive"))
      (node (ref "R508") (pin "P$2") (pinfunction "2_P$2") (pintype "passive"))
      (node (ref "R509") (pin "P$2") (pinfunction "2_P$2") (pintype "passive"))
      (node (ref "R605") (pin "P$1") (pinfunction "1_P$1") (pintype "passive"))
      (node (ref "R608") (pin "P$2") (pinfunction "2_P$2") (pintype "passive"))
      (node (ref "R609") (pin "P$2") (pinfunction "2_P$2") (pintype "passive"))
      (node (ref "U1") (pin "3") (pinfunction "+IN_3") (pintype "input"))
      (node (ref "U1") (pin "5") (pinfunction "+IN_5") (pintype "input"))
      (node (ref "U101") (pin "3") (pinfunction "+IN_3") (pintype "input"))
      (node (ref "U201") (pin "3") (pinfunction "+IN_3") (pintype "input"))
      (node (ref "U301") (pin "3") (pinfunction "+IN_3") (pintype "input"))
      (node (ref "U401") (pin "3") (pinfunction "+IN_3") (pintype "input"))
      (node (ref "U502") (pin "2") (pinfunction "V-_2") (pintype "power_in"))
      (node (ref "U502") (pin "4") (pinfunction "RLO_4") (pintype "input"))
      (node (ref "U602") (pin "2") (pinfunction "V-_2") (pintype "power_in"))
      (node (ref "U602") (pin "4") (pinfunction "RLO_4") (pintype "input"))
    )
    (net (code "10") (name "Net-(C3-+)") (class "Default")
      (node (ref "C3") (pin "POS") (pinfunction "+_POS") (pintype "passive"))
      (node (ref "C502") (pin "NEG") (pinfunction "-_NEG") (pintype "passive"))
      (node (ref "D501") (pin "AC1") (pinfunction "~_AC1") (pintype "bidirectional"))
      (node (ref "D501") (pin "AC2") (pinfunction "~{2}_AC2") (pintype "bidirectional"))
      (node (ref "FB501") (pin "P$1") (pinfunction "1_P$1") (pintype "passive"))
      (node (ref "R508") (pin "P$1") (pinfunction "1_P$1") (pintype "passive"))
    )
    (net (code "11") (name "Net-(C3--)") (class "Default")
      (node (ref "C3") (pin "NEG") (pinfunction "-_NEG") (pintype "passive"))
      (node (ref "R4") (pin "P$1") (pinfunction "1_P$1") (pintype "passive"))
    )
    (net (code "12") (name "Net-(C4-+)") (class "Default")
      (node (ref "C4") (pin "POS") (pinfunction "+_POS") (pintype "passive"))
      (node (ref "R6") (pin "P$2") (pinfunction "2_P$2") (pintype "passive"))
      (node (ref "U502") (pin "5") (pinfunction "SIGIN_5") (pintype "input"))
    )
    (net (code "13") (name "Net-(C5-+)") (class "Default")
      (node (ref "C5") (pin "POS") (pinfunction "+_POS") (pintype "passive"))
      (node (ref "C602") (pin "NEG") (pinfunction "-_NEG") (pintype "passive"))
      (node (ref "D601") (pin "AC1") (pinfunction "~_AC1") (pintype "bidirectional"))
      (node (ref "D601") (pin "AC2") (pinfunction "~{2}_AC2") (pintype "bidirectional"))
      (node (ref "FB601") (pin "P$1") (pinfunction "1_P$1") (pintype "passive"))
      (node (ref "R608") (pin "P$1") (pinfunction "1_P$1") (pintype "passive"))
    )
    (net (code "14") (name "Net-(C5--)") (class "Default")
      (node (ref "C5") (pin "NEG") (pinfunction "-_NEG") (pintype "passive"))
      (node (ref "R1") (pin "P$1") (pinfunction "1_P$1") (pintype "passive"))
    )
    (net (code "15") (name "Net-(C6-+)") (class "Default")
      (node (ref "C6") (pin "POS") (pinfunction "+_POS") (pintype "passive"))
      (node (ref "R3") (pin "P$2") (pinfunction "2_P$2") (pintype "passive"))
      (node (ref "U602") (pin "5") (pinfunction "SIGIN_5") (pintype "input"))
    )
    (net (code "16") (name "Net-(C101-1)") (class "Default")
      (node (ref "C101") (pin "P$1") (pinfunction "1_P$1") (pintype "passive"))
      (node (ref "J101") (pin "2") (pinfunction "2_2") (pintype "passive"))
    )
    (net (code "17") (name "Net-(C101-2)") (class "Default")
      (node (ref "C101") (pin "P$2") (pinfunction "2_P$2") (pintype "passive"))
      (node (ref "C103") (pin "P$2") (pinfunction "2_P$2") (pintype "passive"))
      (node (ref "C104") (pin "P$1") (pinfunction "1_P$1") (pintype "passive"))
    )
    (net (code "18") (name "Net-(C102-1)") (class "Default")
      (node (ref "C102") (pin "P$1") (pinfunction "1_P$1") (pintype "passive"))
      (node (ref "J102") (pin "2") (pinfunction "2_2") (pintype "passive"))
    )
    (net (code "19") (name "Net-(C102-2)") (class "Default")
      (node (ref "C102") (pin "P$2") (pinfunction "2_P$2") (pintype "passive"))
      (node (ref "C105") (pin "P$2") (pinfunction "2_P$2") (pintype "passive"))
      (node (ref "C106") (pin "P$1") (pinfunction "1_P$1") (pintype "passive"))
    )
    (net (code "20") (name "Net-(C103-1)") (class "Default")
      (node (ref "C103") (pin "P$1") (pinfunction "1_P$1") (pintype "passive"))
      (node (ref "C107") (pin "POS") (pinfunction "+_POS") (pintype "passive"))
      (node (ref "J101") (pin "3") (pinfunction "3_3") (pintype "passive"))
      (node (ref "R101") (pin "P$1") (pinfunction "1_P$1") (pintype "passive"))
    )
    (net (code "21") (name "Net-(C104-2)") (class "Default")
      (node (ref "C104") (pin "P$2") (pinfunction "2_P$2") (pintype "passive"))
      (node (ref "C108") (pin "POS") (pinfunction "+_POS") (pintype "passive"))
      (node (ref "J101") (pin "1") (pinfunction "1_1") (pintype "passive"))
      (node (ref "R102") (pin "P$1") (pinfunction "1_P$1") (pintype "passive"))
    )
    (net (code "22") (name "Net-(C105-1)") (class "Default")
      (node (ref "C105") (pin "P$1") (pinfunction "1_P$1") (pintype "passive"))
      (node (ref "C109") (pin "POS") (pinfunction "+_POS") (pintype "passive"))
      (node (ref "J102") (pin "3") (pinfunction "3_3") (pintype "passive"))
    )
    (net (code "23") (name "Net-(C106-2)") (class "Default")
      (node (ref "C106") (pin "P$2") (pinfunction "2_P$2") (pintype "passive"))
      (node (ref "C110") (pin "POS") (pinfunction "+_POS") (pintype "passive"))
      (node (ref "J102") (pin "1") (pinfunction "1_1") (pintype "passive"))
    )
    (net (code "24") (name "Net-(C107--)") (class "Default")
      (node (ref "C107") (pin "NEG") (pinfunction "-_NEG") (pintype "passive"))
      (node (ref "R103") (pin "P$2") (pinfunction "2_P$2") (pintype "passive"))
    )
    (net (code "25") (name "Net-(C108--)") (class "Default")
      (node (ref "C108") (pin "NEG") (pinfunction "-_NEG") (pintype "passive"))
      (node (ref "R104") (pin "P$2") (pinfunction "2_P$2") (pintype "passive"))
    )
    (net (code "26") (name "Net-(C109--)") (class "Default")
      (node (ref "C109") (pin "NEG") (pinfunction "-_NEG") (pintype "passive"))
      (node (ref "R105") (pin "P$2") (pinfunction "2_P$2") (pintype "passive"))
    )
    (net (code "27") (name "Net-(C110--)") (class "Default")
      (node (ref "C110") (pin "NEG") (pinfunction "-_NEG") (pintype "passive"))
      (node (ref "R106") (pin "P$2") (pinfunction "2_P$2") (pintype "passive"))
    )
    (net (code "28") (name "Net-(C111-+)") (class "Default")
      (node (ref "C111") (pin "POS") (pinfunction "+_POS") (pintype "passive"))
      (node (ref "R110") (pin "P$2") (pinfunction "2_P$2") (pintype "passive"))
    )
    (net (code "29") (name "Net-(C111--)") (class "Default")
      (node (ref "C111") (pin "NEG") (pinfunction "-_NEG") (pintype "passive"))
      (node (ref "D103") (pin "A") (pinfunction "A_A") (pintype "passive"))
      (node (ref "IC101") (pin "8") (pinfunction "RG2_8") (pintype "bidirectional"))
    )
    (net (code "30") (name "Net-(C114-+)") (class "Default")
      (node (ref "C114") (pin "POS") (pinfunction "+_POS") (pintype "passive"))
      (node (ref "IC101") (pin "6") (pinfunction "OUT_6") (pintype "bidirectional"))
    )
    (net (code "31") (name "Net-(C114--)") (class "Default")
      (node (ref "C114") (pin "NEG") (pinfunction "-_NEG") (pintype "passive"))
      (node (ref "J104") (pin "1") (pinfunction "1_1") (pintype "passive"))
      (node (ref "R112") (pin "P$1") (pinfunction "1_P$1") (pintype "passive"))
      (node (ref "R116") (pin "P$1") (pinfunction "1_P$1") (pintype "passive"))
    )
    (net (code "32") (name "Net-(C115-1)") (class "Default")
      (node (ref "C115") (pin "P$1") (pinfunction "1_P$1") (pintype "passive"))
      (node (ref "R111") (pin "P$1") (pinfunction "1_P$1") (pintype "passive"))
      (node (ref "VR102") (pin "CCW") (pinfunction "A_CCW") (pintype "passive"))
    )
    (net (code "33") (name "Net-(C115-2)") (class "Default")
      (node (ref "C115") (pin "P$2") (pinfunction "2_P$2") (pintype "passive"))
      (node (ref "C116") (pin "P$2") (pinfunction "2_P$2") (pintype "passive"))
      (node (ref "R113") (pin "P$2") (pinfunction "2_P$2") (pintype "passive"))
      (node (ref "VR102") (pin "WIP") (pinfunction "S_WIP") (pintype "passive"))
    )
    (net (code "34") (name "Net-(C116-1)") (class "Default")
      (node (ref "C116") (pin "P$1") (pinfunction "1_P$1") (pintype "passive"))
      (node (ref "R112") (pin "P$2") (pinfunction "2_P$2") (pintype "passive"))
      (node (ref "VR102") (pin "CW") (pinfunction "E_CW") (pintype "passive"))
    )
    (net (code "35") (name "Net-(C117-1)") (class "Default")
      (node (ref "C117") (pin "P$1") (pinfunction "1_P$1") (pintype "passive"))
      (node (ref "R115") (pin "P$1") (pinfunction "1_P$1") (pintype "passive"))
    )
    (net (code "36") (name "Net-(C117-2)") (class "Default")
      (node (ref "C117") (pin "P$2") (pinfunction "2_P$2") (pintype "passive"))
      (node (ref "VR103") (pin "CCW") (pinfunction "A_CCW") (pintype "passive"))
    )
    (net (code "37") (name "Net-(C118-1)") (class "Default")
      (node (ref "C118") (pin "P$1") (pinfunction "1_P$1") (pintype "passive"))
      (node (ref "VR103") (pin "CW") (pinfunction "E_CW") (pintype "passive"))
    )
    (net (code "38") (name "Net-(C118-2)") (class "Default")
      (node (ref "C118") (pin "P$2") (pinfunction "2_P$2") (pintype "passive"))
      (node (ref "R116") (pin "P$2") (pinfunction "2_P$2") (pintype "passive"))
    )
    (net (code "39") (name "Net-(C119-1)") (class "Default")
      (node (ref "C119") (pin "P$1") (pinfunction "1_P$1") (pintype "passive"))
      (node (ref "R113") (pin "P$1") (pinfunction "1_P$1") (pintype "passive"))
      (node (ref "R114") (pin "P$2") (pinfunction "2_P$2") (pintype "passive"))
      (node (ref "U101") (pin "2") (pinfunction "-IN_2") (pintype "input"))
    )
    (net (code "40") (name "Net-(C119-2)") (class "Default")
      (node (ref "C119") (pin "P$2") (pinfunction "2_P$2") (pintype "passive"))
      (node (ref "C120") (pin "POS") (pinfunction "+_POS") (pintype "passive"))
      (node (ref "R111") (pin "P$2") (pinfunction "2_P$2") (pintype "passive"))
      (node (ref "R115") (pin "P$2") (pinfunction "2_P$2") (pintype "passive"))
      (node (ref "U101") (pin "6") (pinfunction "OUT_6") (pintype "output"))
    )
    (net (code "41") (name "Net-(C120--)") (class "Default")
      (node (ref "C120") (pin "NEG") (pinfunction "-_NEG") (pintype "passive"))
      (node (ref "J105") (pin "1") (pinfunction "1_1") (pintype "passive"))
      (node (ref "J106") (pin "1") (pinfunction "1_1") (pintype "passive"))
    )
    (net (code "42") (name "Net-(C201-1)") (class "Default")
      (node (ref "C201") (pin "P$1") (pinfunction "1_P$1") (pintype "passive"))
      (node (ref "J201") (pin "2") (pinfunction "2_2") (pintype "passive"))
    )
    (net (code "43") (name "Net-(C201-2)") (class "Default")
      (node (ref "C201") (pin "P$2") (pinfunction "2_P$2") (pintype "passive"))
      (node (ref "C203") (pin "P$2") (pinfunction "2_P$2") (pintype "passive"))
      (node (ref "C204") (pin "P$1") (pinfunction "1_P$1") (pintype "passive"))
    )
    (net (code "44") (name "Net-(C202-1)") (class "Default")
      (node (ref "C202") (pin "P$1") (pinfunction "1_P$1") (pintype "passive"))
      (node (ref "J202") (pin "2") (pinfunction "2_2") (pintype "passive"))
    )
    (net (code "45") (name "Net-(C202-2)") (class "Default")
      (node (ref "C202") (pin "P$2") (pinfunction "2_P$2") (pintype "passive"))
      (node (ref "C205") (pin "P$2") (pinfunction "2_P$2") (pintype "passive"))
      (node (ref "C206") (pin "P$1") (pinfunction "1_P$1") (pintype "passive"))
    )
    (net (code "46") (name "Net-(C203-1)") (class "Default")
      (node (ref "C203") (pin "P$1") (pinfunction "1_P$1") (pintype "passive"))
      (node (ref "C207") (pin "POS") (pinfunction "+_POS") (pintype "passive"))
      (node (ref "J201") (pin "3") (pinfunction "3_3") (pintype "passive"))
      (node (ref "R201") (pin "P$1") (pinfunction "1_P$1") (pintype "passive"))
    )
    (net (code "47") (name "Net-(C204-2)") (class "Default")
      (node (ref "C204") (pin "P$2") (pinfunction "2_P$2") (pintype "passive"))
      (node (ref "C208") (pin "POS") (pinfunction "+_POS") (pintype "passive"))
      (node (ref "J201") (pin "1") (pinfunction "1_1") (pintype "passive"))
      (node (ref "R202") (pin "P$1") (pinfunction "1_P$1") (pintype "passive"))
    )
    (net (code "48") (name "Net-(C205-1)") (class "Default")
      (node (ref "C205") (pin "P$1") (pinfunction "1_P$1") (pintype "passive"))
      (node (ref "C209") (pin "POS") (pinfunction "+_POS") (pintype "passive"))
      (node (ref "J202") (pin "3") (pinfunction "3_3") (pintype "passive"))
    )
    (net (code "49") (name "Net-(C206-2)") (class "Default")
      (node (ref "C206") (pin "P$2") (pinfunction "2_P$2") (pintype "passive"))
      (node (ref "C210") (pin "POS") (pinfunction "+_POS") (pintype "passive"))
      (node (ref "J202") (pin "1") (pinfunction "1_1") (pintype "passive"))
    )
    (net (code "50") (name "Net-(C207--)") (class "Default")
      (node (ref "C207") (pin "NEG") (pinfunction "-_NEG") (pintype "passive"))
      (node (ref "R203") (pin "P$2") (pinfunction "2_P$2") (pintype "passive"))
    )
    (net (code "51") (name "Net-(C208--)") (class "Default")
      (node (ref "C208") (pin "NEG") (pinfunction "-_NEG") (pintype "passive"))
      (node (ref "R204") (pin "P$2") (pinfunction "2_P$2") (pintype "passive"))
    )
    (net (code "52") (name "Net-(C209--)") (class "Default")
      (node (ref "C209") (pin "NEG") (pinfunction "-_NEG") (pintype "passive"))
      (node (ref "R205") (pin "P$2") (pinfunction "2_P$2") (pintype "passive"))
    )
    (net (code "53") (name "Net-(C210--)") (class "Default")
      (node (ref "C210") (pin "NEG") (pinfunction "-_NEG") (pintype "passive"))
      (node (ref "R206") (pin "P$2") (pinfunction "2_P$2") (pintype "passive"))
    )
    (net (code "54") (name "Net-(C211-+)") (class "Default")
      (node (ref "C211") (pin "POS") (pinfunction "+_POS") (pintype "passive"))
      (node (ref "R210") (pin "P$2") (pinfunction "2_P$2") (pintype "passive"))
    )
    (net (code "55") (name "Net-(C211--)") (class "Default")
      (node (ref "C211") (pin "NEG") (pinfunction "-_NEG") (pintype "passive"))
      (node (ref "D203") (pin "A") (pinfunction "A_A") (pintype "passive"))
      (node (ref "IC201") (pin "8") (pinfunction "RG2_8") (pintype "bidirectional"))
    )
    (net (code "56") (name "Net-(C214-+)") (class "Default")
      (node (ref "C214") (pin "POS") (pinfunction "+_POS") (pintype "passive"))
      (node (ref "IC201") (pin "6") (pinfunction "OUT_6") (pintype "bidirectional"))
    )
    (net (code "57") (name "Net-(C214--)") (class "Default")
      (node (ref "C214") (pin "NEG") (pinfunction "-_NEG") (pintype "passive"))
      (node (ref "J204") (pin "1") (pinfunction "1_1") (pintype "passive"))
      (node (ref "R212") (pin "P$1") (pinfunction "1_P$1") (pintype "passive"))
      (node (ref "R216") (pin "P$1") (pinfunction "1_P$1") (pintype "passive"))
    )
    (net (code "58") (name "Net-(C215-1)") (class "Default")
      (node (ref "C215") (pin "P$1") (pinfunction "1_P$1") (pintype "passive"))
      (node (ref "R211") (pin "P$1") (pinfunction "1_P$1") (pintype "passive"))
      (node (ref "VR202") (pin "CCW") (pinfunction "A_CCW") (pintype "passive"))
    )
    (net (code "59") (name "Net-(C215-2)") (class "Default")
      (node (ref "C215") (pin "P$2") (pinfunction "2_P$2") (pintype "passive"))
      (node (ref "C216") (pin "P$2") (pinfunction "2_P$2") (pintype "passive"))
      (node (ref "R213") (pin "P$2") (pinfunction "2_P$2") (pintype "passive"))
      (node (ref "VR202") (pin "WIP") (pinfunction "S_WIP") (pintype "passive"))
    )
    (net (code "60") (name "Net-(C216-1)") (class "Default")
      (node (ref "C216") (pin "P$1") (pinfunction "1_P$1") (pintype "passive"))
      (node (ref "R212") (pin "P$2") (pinfunction "2_P$2") (pintype "passive"))
      (node (ref "VR202") (pin "CW") (pinfunction "E_CW") (pintype "passive"))
    )
    (net (code "61") (name "Net-(C217-1)") (class "Default")
      (node (ref "C217") (pin "P$1") (pinfunction "1_P$1") (pintype "passive"))
      (node (ref "R215") (pin "P$1") (pinfunction "1_P$1") (pintype "passive"))
    )
    (net (code "62") (name "Net-(C217-2)") (class "Default")
      (node (ref "C217") (pin "P$2") (pinfunction "2_P$2") (pintype "passive"))
      (node (ref "VR203") (pin "CCW") (pinfunction "A_CCW") (pintype "passive"))
    )
    (net (code "63") (name "Net-(C218-1)") (class "Default")
      (node (ref "C218") (pin "P$1") (pinfunction "1_P$1") (pintype "passive"))
      (node (ref "VR203") (pin "CW") (pinfunction "E_CW") (pintype "passive"))
    )
    (net (code "64") (name "Net-(C218-2)") (class "Default")
      (node (ref "C218") (pin "P$2") (pinfunction "2_P$2") (pintype "passive"))
      (node (ref "R216") (pin "P$2") (pinfunction "2_P$2") (pintype "passive"))
    )
    (net (code "65") (name "Net-(C219-1)") (class "Default")
      (node (ref "C219") (pin "P$1") (pinfunction "1_P$1") (pintype "passive"))
      (node (ref "R213") (pin "P$1") (pinfunction "1_P$1") (pintype "passive"))
      (node (ref "R214") (pin "P$2") (pinfunction "2_P$2") (pintype "passive"))
      (node (ref "U201") (pin "2") (pinfunction "-IN_2") (pintype "input"))
    )
    (net (code "66") (name "Net-(C219-2)") (class "Default")
      (node (ref "C219") (pin "P$2") (pinfunction "2_P$2") (pintype "passive"))
      (node (ref "C220") (pin "POS") (pinfunction "+_POS") (pintype "passive"))
      (node (ref "R211") (pin "P$2") (pinfunction "2_P$2") (pintype "passive"))
      (node (ref "R215") (pin "P$2") (pinfunction "2_P$2") (pintype "passive"))
      (node (ref "U201") (pin "6") (pinfunction "OUT_6") (pintype "output"))
    )
    (net (code "67") (name "Net-(C220--)") (class "Default")
      (node (ref "C220") (pin "NEG") (pinfunction "-_NEG") (pintype "passive"))
      (node (ref "J205") (pin "1") (pinfunction "1_1") (pintype "passive"))
      (node (ref "J206") (pin "1") (pinfunction "1_1") (pintype "passive"))
    )
    (net (code "68") (name "Net-(C301-1)") (class "Default")
      (node (ref "C301") (pin "P$1") (pinfunction "1_P$1") (pintype "passive"))
      (node (ref "J301") (pin "2") (pinfunction "2_2") (pintype "passive"))
    )
    (net (code "69") (name "Net-(C301-2)") (class "Default")
      (node (ref "C301") (pin "P$2") (pinfunction "2_P$2") (pintype "passive"))
      (node (ref "C303") (pin "P$2") (pinfunction "2_P$2") (pintype "passive"))
      (node (ref "C304") (pin "P$1") (pinfunction "1_P$1") (pintype "passive"))
    )
    (net (code "70") (name "Net-(C302-1)") (class "Default")
      (node (ref "C302") (pin "P$1") (pinfunction "1_P$1") (pintype "passive"))
      (node (ref "J302") (pin "2") (pinfunction "2_2") (pintype "passive"))
    )
    (net (code "71") (name "Net-(C302-2)") (class "Default")
      (node (ref "C302") (pin "P$2") (pinfunction "2_P$2") (pintype "passive"))
      (node (ref "C305") (pin "P$2") (pinfunction "2_P$2") (pintype "passive"))
      (node (ref "C306") (pin "P$1") (pinfunction "1_P$1") (pintype "passive"))
    )
    (net (code "72") (name "Net-(C303-1)") (class "Default")
      (node (ref "C303") (pin "P$1") (pinfunction "1_P$1") (pintype "passive"))
      (node (ref "C307") (pin "POS") (pinfunction "+_POS") (pintype "passive"))
      (node (ref "J301") (pin "3") (pinfunction "3_3") (pintype "passive"))
      (node (ref "R301") (pin "P$1") (pinfunction "1_P$1") (pintype "passive"))
    )
    (net (code "73") (name "Net-(C304-2)") (class "Default")
      (node (ref "C304") (pin "P$2") (pinfunction "2_P$2") (pintype "passive"))
      (node (ref "C308") (pin "POS") (pinfunction "+_POS") (pintype "passive"))
      (node (ref "J301") (pin "1") (pinfunction "1_1") (pintype "passive"))
      (node (ref "R302") (pin "P$1") (pinfunction "1_P$1") (pintype "passive"))
    )
    (net (code "74") (name "Net-(C305-1)") (class "Default")
      (node (ref "C305") (pin "P$1") (pinfunction "1_P$1") (pintype "passive"))
      (node (ref "C309") (pin "POS") (pinfunction "+_POS") (pintype "passive"))
      (node (ref "J302") (pin "3") (pinfunction "3_3") (pintype "passive"))
    )
    (net (code "75") (name "Net-(C306-2)") (class "Default")
      (node (ref "C306") (pin "P$2") (pinfunction "2_P$2") (pintype "passive"))
      (node (ref "C310") (pin "POS") (pinfunction "+_POS") (pintype "passive"))
      (node (ref "J302") (pin "1") (pinfunction "1_1") (pintype "passive"))
    )
    (net (code "76") (name "Net-(C307--)") (class "Default")
      (node (ref "C307") (pin "NEG") (pinfunction "-_NEG") (pintype "passive"))
      (node (ref "R303") (pin "P$2") (pinfunction "2_P$2") (pintype "passive"))
    )
    (net (code "77") (name "Net-(C308--)") (class "Default")
      (node (ref "C308") (pin "NEG") (pinfunction "-_NEG") (pintype "passive"))
      (node (ref "R304") (pin "P$2") (pinfunction "2_P$2") (pintype "passive"))
    )
    (net (code "78") (name "Net-(C309--)") (class "Default")
      (node (ref "C309") (pin "NEG") (pinfunction "-_NEG") (pintype "passive"))
      (node (ref "R305") (pin "P$2") (pinfunction "2_P$2") (pintype "passive"))
    )
    (net (code "79") (name "Net-(C310--)") (class "Default")
      (node (ref "C310") (pin "NEG") (pinfunction "-_NEG") (pintype "passive"))
      (node (ref "R306") (pin "P$2") (pinfunction "2_P$2") (pintype "passive"))
    )
    (net (code "80") (name "Net-(C311-+)") (class "Default")
      (node (ref "C311") (pin "POS") (pinfunction "+_POS") (pintype "passive"))
      (node (ref "R310") (pin "P$2") (pinfunction "2_P$2") (pintype "passive"))
    )
    (net (code "81") (name "Net-(C311--)") (class "Default")
      (node (ref "C311") (pin "NEG") (pinfunction "-_NEG") (pintype "passive"))
      (node (ref "D303") (pin "A") (pinfunction "A_A") (pintype "passive"))
      (node (ref "IC301") (pin "8") (pinfunction "RG2_8") (pintype "bidirectional"))
    )
    (net (code "82") (name "Net-(C314-+)") (class "Default")
      (node (ref "C314") (pin "POS") (pinfunction "+_POS") (pintype "passive"))
      (node (ref "IC301") (pin "6") (pinfunction "OUT_6") (pintype "bidirectional"))
    )
    (net (code "83") (name "Net-(C314--)") (class "Default")
      (node (ref "C314") (pin "NEG") (pinfunction "-_NEG") (pintype "passive"))
      (node (ref "J304") (pin "1") (pinfunction "1_1") (pintype "passive"))
      (node (ref "R312") (pin "P$1") (pinfunction "1_P$1") (pintype "passive"))
      (node (ref "R316") (pin "P$1") (pinfunction "1_P$1") (pintype "passive"))
    )
    (net (code "84") (name "Net-(C315-1)") (class "Default")
      (node (ref "C315") (pin "P$1") (pinfunction "1_P$1") (pintype "passive"))
      (node (ref "R311") (pin "P$1") (pinfunction "1_P$1") (pintype "passive"))
      (node (ref "VR302") (pin "CCW") (pinfunction "A_CCW") (pintype "passive"))
    )
    (net (code "85") (name "Net-(C315-2)") (class "Default")
      (node (ref "C315") (pin "P$2") (pinfunction "2_P$2") (pintype "passive"))
      (node (ref "C316") (pin "P$2") (pinfunction "2_P$2") (pintype "passive"))
      (node (ref "R313") (pin "P$2") (pinfunction "2_P$2") (pintype "passive"))
      (node (ref "VR302") (pin "WIP") (pinfunction "S_WIP") (pintype "passive"))
    )
    (net (code "86") (name "Net-(C316-1)") (class "Default")
      (node (ref "C316") (pin "P$1") (pinfunction "1_P$1") (pintype "passive"))
      (node (ref "R312") (pin "P$2") (pinfunction "2_P$2") (pintype "passive"))
      (node (ref "VR302") (pin "CW") (pinfunction "E_CW") (pintype "passive"))
    )
    (net (code "87") (name "Net-(C317-1)") (class "Default")
      (node (ref "C317") (pin "P$1") (pinfunction "1_P$1") (pintype "passive"))
      (node (ref "R315") (pin "P$1") (pinfunction "1_P$1") (pintype "passive"))
    )
    (net (code "88") (name "Net-(C317-2)") (class "Default")
      (node (ref "C317") (pin "P$2") (pinfunction "2_P$2") (pintype "passive"))
      (node (ref "VR303") (pin "CCW") (pinfunction "A_CCW") (pintype "passive"))
    )
    (net (code "89") (name "Net-(C318-1)") (class "Default")
      (node (ref "C318") (pin "P$1") (pinfunction "1_P$1") (pintype "passive"))
      (node (ref "VR303") (pin "CW") (pinfunction "E_CW") (pintype "passive"))
    )
    (net (code "90") (name "Net-(C318-2)") (class "Default")
      (node (ref "C318") (pin "P$2") (pinfunction "2_P$2") (pintype "passive"))
      (node (ref "R316") (pin "P$2") (pinfunction "2_P$2") (pintype "passive"))
    )
    (net (code "91") (name "Net-(C319-1)") (class "Default")
      (node (ref "C319") (pin "P$1") (pinfunction "1_P$1") (pintype "passive"))
      (node (ref "R313") (pin "P$1") (pinfunction "1_P$1") (pintype "passive"))
      (node (ref "R314") (pin "P$2") (pinfunction "2_P$2") (pintype "passive"))
      (node (ref "U301") (pin "2") (pinfunction "-IN_2") (pintype "input"))
    )
    (net (code "92") (name "Net-(C319-2)") (class "Default")
      (node (ref "C319") (pin "P$2") (pinfunction "2_P$2") (pintype "passive"))
      (node (ref "C320") (pin "POS") (pinfunction "+_POS") (pintype "passive"))
      (node (ref "R311") (pin "P$2") (pinfunction "2_P$2") (pintype "passive"))
      (node (ref "R315") (pin "P$2") (pinfunction "2_P$2") (pintype "passive"))
      (node (ref "U301") (pin "6") (pinfunction "OUT_6") (pintype "output"))
    )
    (net (code "93") (name "Net-(C320--)") (class "Default")
      (node (ref "C320") (pin "NEG") (pinfunction "-_NEG") (pintype "passive"))
      (node (ref "J305") (pin "1") (pinfunction "1_1") (pintype "passive"))
      (node (ref "J306") (pin "1") (pinfunction "1_1") (pintype "passive"))
    )
    (net (code "94") (name "Net-(C401-1)") (class "Default")
      (node (ref "C401") (pin "P$1") (pinfunction "1_P$1") (pintype "passive"))
      (node (ref "J401") (pin "2") (pinfunction "2_2") (pintype "passive"))
    )
    (net (code "95") (name "Net-(C401-2)") (class "Default")
      (node (ref "C401") (pin "P$2") (pinfunction "2_P$2") (pintype "passive"))
      (node (ref "C403") (pin "P$2") (pinfunction "2_P$2") (pintype "passive"))
      (node (ref "C404") (pin "P$1") (pinfunction "1_P$1") (pintype "passive"))
    )
    (net (code "96") (name "Net-(C402-1)") (class "Default")
      (node (ref "C402") (pin "P$1") (pinfunction "1_P$1") (pintype "passive"))
      (node (ref "J402") (pin "2") (pinfunction "2_2") (pintype "passive"))
    )
    (net (code "97") (name "Net-(C402-2)") (class "Default")
      (node (ref "C402") (pin "P$2") (pinfunction "2_P$2") (pintype "passive"))
      (node (ref "C405") (pin "P$2") (pinfunction "2_P$2") (pintype "passive"))
      (node (ref "C406") (pin "P$1") (pinfunction "1_P$1") (pintype "passive"))
    )
    (net (code "98") (name "Net-(C403-1)") (class "Default")
      (node (ref "C403") (pin "P$1") (pinfunction "1_P$1") (pintype "passive"))
      (node (ref "C407") (pin "POS") (pinfunction "+_POS") (pintype "passive"))
      (node (ref "J401") (pin "3") (pinfunction "3_3") (pintype "passive"))
      (node (ref "R401") (pin "P$1") (pinfunction "1_P$1") (pintype "passive"))
    )
    (net (code "99") (name "Net-(C404-2)") (class "Default")
      (node (ref "C404") (pin "P$2") (pinfunction "2_P$2") (pintype "passive"))
      (node (ref "C408") (pin "POS") (pinfunction "+_POS") (pintype "passive"))
      (node (ref "J401") (pin "1") (pinfunction "1_1") (pintype "passive"))
      (node (ref "R402") (pin "P$1") (pinfunction "1_P$1") (pintype "passive"))
    )
    (net (code "100") (name "Net-(C405-1)") (class "Default")
      (node (ref "C405") (pin "P$1") (pinfunction "1_P$1") (pintype "passive"))
      (node (ref "C409") (pin "POS") (pinfunction "+_POS") (pintype "passive"))
      (node (ref "J402") (pin "3") (pinfunction "3_3") (pintype "passive"))
    )
    (net (code "101") (name "Net-(C406-2)") (class "Default")
      (node (ref "C406") (pin "P$2") (pinfunction "2_P$2") (pintype "passive"))
      (node (ref "C410") (pin "POS") (pinfunction "+_POS") (pintype "passive"))
      (node (ref "J402") (pin "1") (pinfunction "1_1") (pintype "passive"))
    )
    (net (code "102") (name "Net-(C407--)") (class "Default")
      (node (ref "C407") (pin "NEG") (pinfunction "-_NEG") (pintype "passive"))
      (node (ref "R403") (pin "P$2") (pinfunction "2_P$2") (pintype "passive"))
    )
    (net (code "103") (name "Net-(C408--)") (class "Default")
      (node (ref "C408") (pin "NEG") (pinfunction "-_NEG") (pintype "passive"))
      (node (ref "R404") (pin "P$2") (pinfunction "2_P$2") (pintype "passive"))
    )
    (net (code "104") (name "Net-(C409--)") (class "Default")
      (node (ref "C409") (pin "NEG") (pinfunction "-_NEG") (pintype "passive"))
      (node (ref "R405") (pin "P$2") (pinfunction "2_P$2") (pintype "passive"))
    )
    (net (code "105") (name "Net-(C410--)") (class "Default")
      (node (ref "C410") (pin "NEG") (pinfunction "-_NEG") (pintype "passive"))
      (node (ref "R406") (pin "P$2") (pinfunction "2_P$2") (pintype "passive"))
    )
    (net (code "106") (name "Net-(C411-+)") (class "Default")
      (node (ref "C411") (pin "POS") (pinfunction "+_POS") (pintype "passive"))
      (node (ref "R410") (pin "P$2") (pinfunction "2_P$2") (pintype "passive"))
    )
    (net (code "107") (name "Net-(C411--)") (class "Default")
      (node (ref "C411") (pin "NEG") (pinfunction "-_NEG") (pintype "passive"))
      (node (ref "D403") (pin "A") (pinfunction "A_A") (pintype "passive"))
      (node (ref "IC401") (pin "8") (pinfunction "RG2_8") (pintype "bidirectional"))
    )
    (net (code "108") (name "Net-(C414-+)") (class "Default")
      (node (ref "C414") (pin "POS") (pinfunction "+_POS") (pintype "passive"))
      (node (ref "IC401") (pin "6") (pinfunction "OUT_6") (pintype "bidirectional"))
    )
    (net (code "109") (name "Net-(C414--)") (class "Default")
      (node (ref "C414") (pin "NEG") (pinfunction "-_NEG") (pintype "passive"))
      (node (ref "J404") (pin "1") (pinfunction "1_1") (pintype "passive"))
      (node (ref "R412") (pin "P$1") (pinfunction "1_P$1") (pintype "passive"))
      (node (ref "R416") (pin "P$1") (pinfunction "1_P$1") (pintype "passive"))
    )
    (net (code "110") (name "Net-(C415-1)") (class "Default")
      (node (ref "C415") (pin "P$1") (pinfunction "1_P$1") (pintype "passive"))
      (node (ref "R411") (pin "P$1") (pinfunction "1_P$1") (pintype "passive"))
      (node (ref "VR402") (pin "CCW") (pinfunction "A_CCW") (pintype "passive"))
    )
    (net (code "111") (name "Net-(C415-2)") (class "Default")
      (node (ref "C415") (pin "P$2") (pinfunction "2_P$2") (pintype "passive"))
      (node (ref "C416") (pin "P$2") (pinfunction "2_P$2") (pintype "passive"))
      (node (ref "R413") (pin "P$2") (pinfunction "2_P$2") (pintype "passive"))
      (node (ref "VR402") (pin "WIP") (pinfunction "S_WIP") (pintype "passive"))
    )
    (net (code "112") (name "Net-(C416-1)") (class "Default")
      (node (ref "C416") (pin "P$1") (pinfunction "1_P$1") (pintype "passive"))
      (node (ref "R412") (pin "P$2") (pinfunction "2_P$2") (pintype "passive"))
      (node (ref "VR402") (pin "CW") (pinfunction "E_CW") (pintype "passive"))
    )
    (net (code "113") (name "Net-(C417-1)") (class "Default")
      (node (ref "C417") (pin "P$1") (pinfunction "1_P$1") (pintype "passive"))
      (node (ref "R415") (pin "P$1") (pinfunction "1_P$1") (pintype "passive"))
    )
    (net (code "114") (name "Net-(C417-2)") (class "Default")
      (node (ref "C417") (pin "P$2") (pinfunction "2_P$2") (pintype "passive"))
      (node (ref "VR403") (pin "CCW") (pinfunction "A_CCW") (pintype "passive"))
    )
    (net (code "115") (name "Net-(C418-1)") (class "Default")
      (node (ref "C418") (pin "P$1") (pinfunction "1_P$1") (pintype "passive"))
      (node (ref "VR403") (pin "CW") (pinfunction "E_CW") (pintype "passive"))
    )
    (net (code "116") (name "Net-(C418-2)") (class "Default")
      (node (ref "C418") (pin "P$2") (pinfunction "2_P$2") (pintype "passive"))
      (node (ref "R416") (pin "P$2") (pinfunction "2_P$2") (pintype "passive"))
    )
    (net (code "117") (name "Net-(C419-1)") (class "Default")
      (node (ref "C419") (pin "P$1") (pinfunction "1_P$1") (pintype "passive"))
      (node (ref "R413") (pin "P$1") (pinfunction "1_P$1") (pintype "passive"))
      (node (ref "R414") (pin "P$2") (pinfunction "2_P$2") (pintype "passive"))
      (node (ref "U401") (pin "2") (pinfunction "-IN_2") (pintype "input"))
    )
    (net (code "118") (name "Net-(C419-2)") (class "Default")
      (node (ref "C419") (pin "P$2") (pinfunction "2_P$2") (pintype "passive"))
      (node (ref "C420") (pin "POS") (pinfunction "+_POS") (pintype "passive"))
      (node (ref "R411") (pin "P$2") (pinfunction "2_P$2") (pintype "passive"))
      (node (ref "R415") (pin "P$2") (pinfunction "2_P$2") (pintype "passive"))
      (node (ref "U401") (pin "6") (pinfunction "OUT_6") (pintype "output"))
    )
    (net (code "119") (name "Net-(C420--)") (class "Default")
      (node (ref "C420") (pin "NEG") (pinfunction "-_NEG") (pintype "passive"))
      (node (ref "J405") (pin "1") (pinfunction "1_1") (pintype "passive"))
      (node (ref "J406") (pin "1") (pinfunction "1_1") (pintype "passive"))
    )
    (net (code "120") (name "Net-(C501-1)") (class "Default")
      (node (ref "C501") (pin "P$1") (pinfunction "1_P$1") (pintype "passive"))
      (node (ref "R501") (pin "P$1") (pinfunction "1_P$1") (pintype "passive"))
      (node (ref "R502") (pin "P$1") (pinfunction "1_P$1") (pintype "passive"))
      (node (ref "R503") (pin "P$1") (pinfunction "1_P$1") (pintype "passive"))
      (node (ref "R504") (pin "P$1") (pinfunction "1_P$1") (pintype "passive"))
      (node (ref "R506") (pin "P$2") (pinfunction "2_P$2") (pintype "passive"))
      (node (ref "U501") (pin "2") (pinfunction "-IN_2") (pintype "input"))
    )
    (net (code "121") (name "Net-(C501-2)") (class "Default")
      (node (ref "C501") (pin "P$2") (pinfunction "2_P$2") (pintype "passive"))
      (node (ref "R507") (pin "P$2") (pinfunction "2_P$2") (pintype "passive"))
      (node (ref "U501") (pin "6") (pinfunction "OUT_6") (pintype "output"))
    )
    (net (code "122") (name "Net-(C502-+)") (class "Default")
      (node (ref "C502") (pin "POS") (pinfunction "+_POS") (pintype "passive"))
      (node (ref "R506") (pin "P$1") (pinfunction "1_P$1") (pintype "passive"))
      (node (ref "R507") (pin "P$1") (pinfunction "1_P$1") (pintype "passive"))
    )
    (net (code "123") (name "Net-(C505-1)") (class "Default")
      (node (ref "C505") (pin "P$1") (pinfunction "1_P$1") (pintype "passive"))
      (node (ref "FB501") (pin "P$2") (pinfunction "2_P$2") (pintype "passive"))
      (node (ref "J501") (pin "1") (pinfunction "1_1") (pintype "passive"))
    )
    (net (code "124") (name "Net-(C601-1)") (class "Default")
      (node (ref "C601") (pin "P$1") (pinfunction "1_P$1") (pintype "passive"))
      (node (ref "R601") (pin "P$1") (pinfunction "1_P$1") (pintype "passive"))
      (node (ref "R602") (pin "P$1") (pinfunction "1_P$1") (pintype "passive"))
      (node (ref "R603") (pin "P$1") (pinfunction "1_P$1") (pintype "passive"))
      (node (ref "R604") (pin "P$1") (pinfunction "1_P$1") (pintype "passive"))
      (node (ref "R606") (pin "P$2") (pinfunction "2_P$2") (pintype "passive"))
      (node (ref "U601") (pin "2") (pinfunction "-IN_2") (pintype "input"))
    )
    (net (code "125") (name "Net-(C601-2)") (class "Default")
      (node (ref "C601") (pin "P$2") (pinfunction "2_P$2") (pintype "passive"))
      (node (ref "R607") (pin "P$2") (pinfunction "2_P$2") (pintype "passive"))
      (node (ref "U601") (pin "6") (pinfunction "OUT_6") (pintype "output"))
    )
    (net (code "126") (name "Net-(C602-+)") (class "Default")
      (node (ref "C602") (pin "POS") (pinfunction "+_POS") (pintype "passive"))
      (node (ref "R606") (pin "P$1") (pinfunction "1_P$1") (pintype "passive"))
      (node (ref "R607") (pin "P$1") (pinfunction "1_P$1") (pintype "passive"))
    )
    (net (code "127") (name "Net-(C605-1)") (class "Default")
      (node (ref "C605") (pin "P$1") (pinfunction "1_P$1") (pintype "passive"))
      (node (ref "FB601") (pin "P$2") (pinfunction "2_P$2") (pintype "passive"))
      (node (ref "J601") (pin "1") (pinfunction "1_1") (pintype "passive"))
    )
    (net (code "128") (name "Net-(D101-~)") (class "Default")
      (node (ref "D101") (pin "AC1") (pinfunction "~_AC1") (pintype "bidirectional"))
      (node (ref "D103") (pin "C") (pinfunction "C_C") (pintype "passive"))
      (node (ref "IC101") (pin "3") (pinfunction "+IN_3") (pintype "bidirectional"))
      (node (ref "R104") (pin "P$1") (pinfunction "1_P$1") (pintype "passive"))
      (node (ref "R106") (pin "P$1") (pinfunction "1_P$1") (pintype "passive"))
      (node (ref "R109") (pin "P$2") (pinfunction "2_P$2") (pintype "passive"))
    )
    (net (code "129") (name "Net-(D101-~{2})") (class "Default")
      (node (ref "D101") (pin "AC2") (pinfunction "~{2}_AC2") (pintype "bidirectional"))
      (node (ref "D102") (pin "C") (pinfunction "C_C") (pintype "passive"))
      (node (ref "IC101") (pin "2") (pinfunction "-IN_2") (pintype "bidirectional"))
      (node (ref "R103") (pin "P$1") (pinfunction "1_P$1") (pintype "passive"))
      (node (ref "R105") (pin "P$1") (pinfunction "1_P$1") (pintype "passive"))
      (node (ref "R108") (pin "P$1") (pinfunction "1_P$1") (pintype "passive"))
    )
    (net (code "130") (name "Net-(D201-~)") (class "Default")
      (node (ref "D201") (pin "AC1") (pinfunction "~_AC1") (pintype "bidirectional"))
      (node (ref "D203") (pin "C") (pinfunction "C_C") (pintype "passive"))
      (node (ref "IC201") (pin "3") (pinfunction "+IN_3") (pintype "bidirectional"))
      (node (ref "R204") (pin "P$1") (pinfunction "1_P$1") (pintype "passive"))
      (node (ref "R206") (pin "P$1") (pinfunction "1_P$1") (pintype "passive"))
      (node (ref "R209") (pin "P$2") (pinfunction "2_P$2") (pintype "passive"))
    )
    (net (code "131") (name "Net-(D201-~{2})") (class "Default")
      (node (ref "D201") (pin "AC2") (pinfunction "~{2}_AC2") (pintype "bidirectional"))
      (node (ref "D202") (pin "C") (pinfunction "C_C") (pintype "passive"))
      (node (ref "IC201") (pin "2") (pinfunction "-IN_2") (pintype "bidirectional"))
      (node (ref "R203") (pin "P$1") (pinfunction "1_P$1") (pintype "passive"))
      (node (ref "R205") (pin "P$1") (pinfunction "1_P$1") (pintype "passive"))
      (node (ref "R208") (pin "P$1") (pinfunction "1_P$1") (pintype "passive"))
    )
    (net (code "132") (name "Net-(D301-~)") (class "Default")
      (node (ref "D301") (pin "AC1") (pinfunction "~_AC1") (pintype "bidirectional"))
      (node (ref "D303") (pin "C") (pinfunction "C_C") (pintype "passive"))
      (node (ref "IC301") (pin "3") (pinfunction "+IN_3") (pintype "bidirectional"))
      (node (ref "R304") (pin "P$1") (pinfunction "1_P$1") (pintype "passive"))
      (node (ref "R306") (pin "P$1") (pinfunction "1_P$1") (pintype "passive"))
      (node (ref "R309") (pin "P$2") (pinfunction "2_P$2") (pintype "passive"))
    )
    (net (code "133") (name "Net-(D301-~{2})") (class "Default")
      (node (ref "D301") (pin "AC2") (pinfunction "~{2}_AC2") (pintype "bidirectional"))
      (node (ref "D302") (pin "C") (pinfunction "C_C") (pintype "passive"))
      (node (ref "IC301") (pin "2") (pinfunction "-IN_2") (pintype "bidirectional"))
      (node (ref "R303") (pin "P$1") (pinfunction "1_P$1") (pintype "passive"))
      (node (ref "R305") (pin "P$1") (pinfunction "1_P$1") (pintype "passive"))
      (node (ref "R308") (pin "P$1") (pinfunction "1_P$1") (pintype "passive"))
    )
    (net (code "134") (name "Net-(D401-~)") (class "Default")
      (node (ref "D401") (pin "AC1") (pinfunction "~_AC1") (pintype "bidirectional"))
      (node (ref "D403") (pin "C") (pinfunction "C_C") (pintype "passive"))
      (node (ref "IC401") (pin "3") (pinfunction "+IN_3") (pintype "bidirectional"))
      (node (ref "R404") (pin "P$1") (pinfunction "1_P$1") (pintype "passive"))
      (node (ref "R406") (pin "P$1") (pinfunction "1_P$1") (pintype "passive"))
      (node (ref "R409") (pin "P$2") (pinfunction "2_P$2") (pintype "passive"))
    )
    (net (code "135") (name "Net-(D401-~{2})") (class "Default")
      (node (ref "D401") (pin "AC2") (pinfunction "~{2}_AC2") (pintype "bidirectional"))
      (node (ref "D402") (pin "C") (pinfunction "C_C") (pintype "passive"))
      (node (ref "IC401") (pin "2") (pinfunction "-IN_2") (pintype "bidirectional"))
      (node (ref "R403") (pin "P$1") (pinfunction "1_P$1") (pintype "passive"))
      (node (ref "R405") (pin "P$1") (pinfunction "1_P$1") (pintype "passive"))
      (node (ref "R408") (pin "P$1") (pinfunction "1_P$1") (pintype "passive"))
    )
    (net (code "136") (name "Net-(D502-C)") (class "Default")
      (node (ref "D502") (pin "20") (pinfunction "C_20") (pintype "passive"))
      (node (ref "U502") (pin "10") (pinfunction "LED10_10") (pintype "output"))
    )
    (net (code "137") (name "Net-(D502-C1)") (class "Default")
      (node (ref "D502") (pin "19") (pinfunction "C1_19") (pintype "passive"))
      (node (ref "U502") (pin "11") (pinfunction "LED9_11") (pintype "output"))
    )
    (net (code "138") (name "Net-(D502-C2)") (class "Default")
      (node (ref "D502") (pin "18") (pinfunction "C2_18") (pintype "passive"))
      (node (ref "U502") (pin "12") (pinfunction "LED8_12") (pintype "output"))
    )
    (net (code "139") (name "Net-(D502-C3)") (class "Default")
      (node (ref "D502") (pin "17") (pinfunction "C3_17") (pintype "passive"))
      (node (ref "U502") (pin "13") (pinfunction "LED7_13") (pintype "output"))
    )
    (net (code "140") (name "Net-(D502-C4)") (class "Default")
      (node (ref "D502") (pin "16") (pinfunction "C4_16") (pintype "passive"))
      (node (ref "U502") (pin "14") (pinfunction "LED6_14") (pintype "output"))
    )
    (net (code "141") (name "Net-(D502-C5)") (class "Default")
      (node (ref "D502") (pin "15") (pinfunction "C5_15") (pintype "passive"))
      (node (ref "U502") (pin "15") (pinfunction "LED5_15") (pintype "output"))
    )
    (net (code "142") (name "Net-(D502-C6)") (class "Default")
      (node (ref "D502") (pin "14") (pinfunction "C6_14") (pintype "passive"))
      (node (ref "U502") (pin "16") (pinfunction "LED4_16") (pintype "output"))
    )
    (net (code "143") (name "Net-(D502-C7)") (class "Default")
      (node (ref "D502") (pin "13") (pinfunction "C7_13") (pintype "passive"))
      (node (ref "U502") (pin "17") (pinfunction "LED3_17") (pintype "output"))
    )
    (net (code "144") (name "Net-(D502-C8)") (class "Default")
      (node (ref "D502") (pin "12") (pinfunction "C8_12") (pintype "passive"))
      (node (ref "U502") (pin "18") (pinfunction "LED2_18") (pintype "output"))
    )
    (net (code "145") (name "Net-(D502-C9)") (class "Default")
      (node (ref "D502") (pin "11") (pinfunction "C9_11") (pintype "passive"))
      (node (ref "U502") (pin "1") (pinfunction "LED1_1") (pintype "output"))
    )
    (net (code "146") (name "Net-(D602-C)") (class "Default")
      (node (ref "D602") (pin "20") (pinfunction "C_20") (pintype "passive"))
      (node (ref "U602") (pin "10") (pinfunction "LED10_10") (pintype "output"))
    )
    (net (code "147") (name "Net-(D602-C1)") (class "Default")
      (node (ref "D602") (pin "19") (pinfunction "C1_19") (pintype "passive"))
      (node (ref "U602") (pin "11") (pinfunction "LED9_11") (pintype "output"))
    )
    (net (code "148") (name "Net-(D602-C2)") (class "Default")
      (node (ref "D602") (pin "18") (pinfunction "C2_18") (pintype "passive"))
      (node (ref "U602") (pin "12") (pinfunction "LED8_12") (pintype "output"))
    )
    (net (code "149") (name "Net-(D602-C3)") (class "Default")
      (node (ref "D602") (pin "17") (pinfunction "C3_17") (pintype "passive"))
      (node (ref "U602") (pin "13") (pinfunction "LED7_13") (pintype "output"))
    )
    (net (code "150") (name "Net-(D602-C4)") (class "Default")
      (node (ref "D602") (pin "16") (pinfunction "C4_16") (pintype "passive"))
      (node (ref "U602") (pin "14") (pinfunction "LED6_14") (pintype "output"))
    )
    (net (code "151") (name "Net-(D602-C5)") (class "Default")
      (node (ref "D602") (pin "15") (pinfunction "C5_15") (pintype "passive"))
      (node (ref "U602") (pin "15") (pinfunction "LED5_15") (pintype "output"))
    )
    (net (code "152") (name "Net-(D602-C6)") (class "Default")
      (node (ref "D602") (pin "14") (pinfunction "C6_14") (pintype "passive"))
      (node (ref "U602") (pin "16") (pinfunction "LED4_16") (pintype "output"))
    )
    (net (code "153") (name "Net-(D602-C7)") (class "Default")
      (node (ref "D602") (pin "13") (pinfunction "C7_13") (pintype "passive"))
      (node (ref "U602") (pin "17") (pinfunction "LED3_17") (pintype "output"))
    )
    (net (code "154") (name "Net-(D602-C8)") (class "Default")
      (node (ref "D602") (pin "12") (pinfunction "C8_12") (pintype "passive"))
      (node (ref "U602") (pin "18") (pinfunction "LED2_18") (pintype "output"))
    )
    (net (code "155") (name "Net-(D602-C9)") (class "Default")
      (node (ref "D602") (pin "11") (pinfunction "C9_11") (pintype "passive"))
      (node (ref "U602") (pin "1") (pinfunction "LED1_1") (pintype "output"))
    )
    (net (code "156") (name "Net-(IC101-RG1)") (class "Default")
      (node (ref "D102") (pin "A") (pinfunction "A_A") (pintype "passive"))
      (node (ref "IC101") (pin "1") (pinfunction "RG1_1") (pintype "bidirectional"))
      (node (ref "VR101") (pin "CCW") (pinfunction "A_CCW") (pintype "passive"))
      (node (ref "VR101") (pin "WIP") (pinfunction "S_WIP") (pintype "passive"))
    )
    (net (code "157") (name "Net-(IC201-RG1)") (class "Default")
      (node (ref "D202") (pin "A") (pinfunction "A_A") (pintype "passive"))
      (node (ref "IC201") (pin "1") (pinfunction "RG1_1") (pintype "bidirectional"))
      (node (ref "VR201") (pin "CCW") (pinfunction "A_CCW") (pintype "passive"))
      (node (ref "VR201") (pin "WIP") (pinfunction "S_WIP") (pintype "passive"))
    )
    (net (code "158") (name "Net-(IC301-RG1)") (class "Default")
      (node (ref "D302") (pin "A") (pinfunction "A_A") (pintype "passive"))
      (node (ref "IC301") (pin "1") (pinfunction "RG1_1") (pintype "bidirectional"))
      (node (ref "VR301") (pin "CCW") (pinfunction "A_CCW") (pintype "passive"))
      (node (ref "VR301") (pin "WIP") (pinfunction "S_WIP") (pintype "passive"))
    )
    (net (code "159") (name "Net-(IC401-RG1)") (class "Default")
      (node (ref "D402") (pin "A") (pinfunction "A_A") (pintype "passive"))
      (node (ref "IC401") (pin "1") (pinfunction "RG1_1") (pintype "bidirectional"))
      (node (ref "VR401") (pin "CCW") (pinfunction "A_CCW") (pintype "passive"))
      (node (ref "VR401") (pin "WIP") (pinfunction "S_WIP") (pintype "passive"))
    )
    (net (code "160") (name "Net-(R1-2)") (class "Default")
      (node (ref "D1") (pin "A") (pinfunction "A_A") (pintype "passive"))
      (node (ref "R1") (pin "P$2") (pinfunction "2_P$2") (pintype "passive"))
      (node (ref "R2") (pin "P$1") (pinfunction "1_P$1") (pintype "passive"))
      (node (ref "U1") (pin "2") (pinfunction "-IN_2") (pintype "input"))
    )
    (net (code "161") (name "Net-(R2-2)") (class "Default")
      (node (ref "D2") (pin "C") (pinfunction "C_C") (pintype "passive"))
      (node (ref "R2") (pin "P$2") (pinfunction "2_P$2") (pintype "passive"))
      (node (ref "R3") (pin "P$1") (pinfunction "1_P$1") (pintype "passive"))
    )
    (net (code "162") (name "Net-(R4-2)") (class "Default")
      (node (ref "D3") (pin "A") (pinfunction "A_A") (pintype "passive"))
      (node (ref "R4") (pin "P$2") (pinfunction "2_P$2") (pintype "passive"))
      (node (ref "R5") (pin "P$1") (pinfunction "1_P$1") (pintype "passive"))
      (node (ref "U1") (pin "6") (pinfunction "-IN_6") (pintype "input"))
    )
    (net (code "163") (name "Net-(R5-2)") (class "Default")
      (node (ref "D4") (pin "C") (pinfunction "C_C") (pintype "passive"))
      (node (ref "R5") (pin "P$2") (pinfunction "2_P$2") (pintype "passive"))
      (node (ref "R6") (pin "P$1") (pinfunction "1_P$1") (pintype "passive"))
    )
    (net (code "164") (name "Net-(R101-2)") (class "Default")
      (node (ref "J103") (pin "1") (pinfunction "1_1") (pintype "passive"))
      (node (ref "R101") (pin "P$2") (pinfunction "2_P$2") (pintype "passive"))
      (node (ref "R102") (pin "P$2") (pinfunction "2_P$2") (pintype "passive"))
    )
    (net (code "165") (name "Net-(R107-1)") (class "Default")
      (node (ref "R107") (pin "P$1") (pinfunction "1_P$1") (pintype "passive"))
      (node (ref "R108") (pin "P$2") (pinfunction "2_P$2") (pintype "passive"))
      (node (ref "R109") (pin "P$1") (pinfunction "1_P$1") (pintype "passive"))
    )
    (net (code "166") (name "Net-(R110-1)") (class "Default")
      (node (ref "R110") (pin "P$1") (pinfunction "1_P$1") (pintype "passive"))
      (node (ref "VR101") (pin "CW") (pinfunction "E_CW") (pintype "passive"))
    )
    (net (code "167") (name "Net-(R114-1)") (class "Default")
      (node (ref "R114") (pin "P$1") (pinfunction "1_P$1") (pintype "passive"))
      (node (ref "VR103") (pin "WIP") (pinfunction "S_WIP") (pintype "passive"))
    )
    (net (code "168") (name "Net-(R201-2)") (class "Default")
      (node (ref "J203") (pin "1") (pinfunction "1_1") (pintype "passive"))
      (node (ref "R201") (pin "P$2") (pinfunction "2_P$2") (pintype "passive"))
      (node (ref "R202") (pin "P$2") (pinfunction "2_P$2") (pintype "passive"))
    )
    (net (code "169") (name "Net-(R207-1)") (class "Default")
      (node (ref "R207") (pin "P$1") (pinfunction "1_P$1") (pintype "passive"))
      (node (ref "R208") (pin "P$2") (pinfunction "2_P$2") (pintype "passive"))
      (node (ref "R209") (pin "P$1") (pinfunction "1_P$1") (pintype "passive"))
    )
    (net (code "170") (name "Net-(R210-1)") (class "Default")
      (node (ref "R210") (pin "P$1") (pinfunction "1_P$1") (pintype "passive"))
      (node (ref "VR201") (pin "CW") (pinfunction "E_CW") (pintype "passive"))
    )
    (net (code "171") (name "Net-(R214-1)") (class "Default")
      (node (ref "R214") (pin "P$1") (pinfunction "1_P$1") (pintype "passive"))
      (node (ref "VR203") (pin "WIP") (pinfunction "S_WIP") (pintype "passive"))
    )
    (net (code "172") (name "Net-(R301-2)") (class "Default")
      (node (ref "J303") (pin "1") (pinfunction "1_1") (pintype "passive"))
      (node (ref "R301") (pin "P$2") (pinfunction "2_P$2") (pintype "passive"))
      (node (ref "R302") (pin "P$2") (pinfunction "2_P$2") (pintype "passive"))
    )
    (net (code "173") (name "Net-(R307-1)") (class "Default")
      (node (ref "R307") (pin "P$1") (pinfunction "1_P$1") (pintype "passive"))
      (node (ref "R308") (pin "P$2") (pinfunction "2_P$2") (pintype "passive"))
      (node (ref "R309") (pin "P$1") (pinfunction "1_P$1") (pintype "passive"))
    )
    (net (code "174") (name "Net-(R310-1)") (class "Default")
      (node (ref "R310") (pin "P$1") (pinfunction "1_P$1") (pintype "passive"))
      (node (ref "VR301") (pin "CW") (pinfunction "E_CW") (pintype "passive"))
    )
    (net (code "175") (name "Net-(R314-1)") (class "Default")
      (node (ref "R314") (pin "P$1") (pinfunction "1_P$1") (pintype "passive"))
      (node (ref "VR303") (pin "WIP") (pinfunction "S_WIP") (pintype "passive"))
    )
    (net (code "176") (name "Net-(R401-2)") (class "Default")
      (node (ref "J403") (pin "1") (pinfunction "1_1") (pintype "passive"))
      (node (ref "R401") (pin "P$2") (pinfunction "2_P$2") (pintype "passive"))
      (node (ref "R402") (pin "P$2") (pinfunction "2_P$2") (pintype "passive"))
    )
    (net (code "177") (name "Net-(R407-1)") (class "Default")
      (node (ref "R407") (pin "P$1") (pinfunction "1_P$1") (pintype "passive"))
      (node (ref "R408") (pin "P$2") (pinfunction "2_P$2") (pintype "passive"))
      (node (ref "R409") (pin "P$1") (pinfunction "1_P$1") (pintype "passive"))
    )
    (net (code "178") (name "Net-(R410-1)") (class "Default")
      (node (ref "R410") (pin "P$1") (pinfunction "1_P$1") (pintype "passive"))
      (node (ref "VR401") (pin "CW") (pinfunction "E_CW") (pintype "passive"))
    )
    (net (code "179") (name "Net-(R414-1)") (class "Default")
      (node (ref "R414") (pin "P$1") (pinfunction "1_P$1") (pintype "passive"))
      (node (ref "VR403") (pin "WIP") (pinfunction "S_WIP") (pintype "passive"))
    )
    (net (code "180") (name "Net-(R505-2)") (class "Default")
      (node (ref "R505") (pin "P$2") (pinfunction "2_P$2") (pintype "passive"))
      (node (ref "U501") (pin "3") (pinfunction "+IN_3") (pintype "input"))
    )
    (net (code "181") (name "Net-(R509-1)") (class "Default")
      (node (ref "R509") (pin "P$1") (pinfunction "1_P$1") (pintype "passive"))
      (node (ref "R510") (pin "P$2") (pinfunction "2_P$2") (pintype "passive"))
      (node (ref "U502") (pin "8") (pinfunction "REFADJ_8") (pintype "passive"))
    )
    (net (code "182") (name "Net-(R510-1)") (class "Default")
      (node (ref "R510") (pin "P$1") (pinfunction "1_P$1") (pintype "passive"))
      (node (ref "R511") (pin "P$2") (pinfunction "2_P$2") (pintype "passive"))
      (node (ref "U502") (pin "7") (pinfunction "REFOUT_7") (pintype "output"))
    )
    (net (code "183") (name "Net-(R511-1)") (class "Default")
      (node (ref "R511") (pin "P$1") (pinfunction "1_P$1") (pintype "passive"))
      (node (ref "U502") (pin "6") (pinfunction "RHI_6") (pintype "input"))
    )
    (net (code "184") (name "Net-(R605-2)") (class "Default")
      (node (ref "R605") (pin "P$2") (pinfunction "2_P$2") (pintype "passive"))
      (node (ref "U601") (pin "3") (pinfunction "+IN_3") (pintype "input"))
    )
    (net (code "185") (name "Net-(R609-1)") (class "Default")
      (node (ref "R609") (pin "P$1") (pinfunction "1_P$1") (pintype "passive"))
      (node (ref "R610") (pin "P$2") (pinfunction "2_P$2") (pintype "passive"))
      (node (ref "U602") (pin "8") (pinfunction "REFADJ_8") (pintype "passive"))
    )
    (net (code "186") (name "Net-(R610-1)") (class "Default")
      (node (ref "R610") (pin "P$1") (pinfunction "1_P$1") (pintype "passive"))
      (node (ref "R611") (pin "P$2") (pinfunction "2_P$2") (pintype "passive"))
      (node (ref "U602") (pin "7") (pinfunction "REFOUT_7") (pintype "output"))
    )
    (net (code "187") (name "Net-(R611-1)") (class "Default")
      (node (ref "R611") (pin "P$1") (pinfunction "1_P$1") (pintype "passive"))
      (node (ref "U602") (pin "6") (pinfunction "RHI_6") (pintype "input"))
    )
    (net (code "188") (name "Net-(R701-2)") (class "Default")
      (node (ref "J701") (pin "3") (pinfunction "3_3") (pintype "passive"))
      (node (ref "R701") (pin "P$2") (pinfunction "2_P$2") (pintype "passive"))
    )
    (net (code "189") (name "Net-(R702-2)") (class "Default")
      (node (ref "J701") (pin "1") (pinfunction "1_1") (pintype "passive"))
      (node (ref "R702") (pin "P$2") (pinfunction "2_P$2") (pintype "passive"))
    )
    (net (code "190") (name "Net-(R703-2)") (class "Default")
      (node (ref "D701") (pin "A") (pinfunction "A_A") (pintype "passive"))
      (node (ref "R703") (pin "P$2") (pinfunction "2_P$2") (pintype "passive"))
    )
    (net (code "191") (name "Net-(U1A-OUT)") (class "Default")
      (node (ref "D1") (pin "C") (pinfunction "C_C") (pintype "passive"))
      (node (ref "D2") (pin "A") (pinfunction "A_A") (pintype "passive"))
      (node (ref "U1") (pin "1") (pinfunction "OUT_1") (pintype "output"))
    )
    (net (code "192") (name "Net-(U1B-OUT)") (class "Default")
      (node (ref "D3") (pin "C") (pinfunction "C_C") (pintype "passive"))
      (node (ref "D4") (pin "A") (pinfunction "A_A") (pintype "passive"))
      (node (ref "U1") (pin "7") (pinfunction "OUT_7") (pintype "output"))
    )
    (net (code "193") (name "VCC") (class "Default")
      (node (ref "C112") (pin "P$1") (pinfunction "1_P$1") (pintype "passive"))
      (node (ref "C121") (pin "P$1") (pinfunction "1_P$1") (pintype "passive"))
      (node (ref "C2") (pin "P$1") (pinfunction "1_P$1") (pintype "passive"))
      (node (ref "C212") (pin "P$1") (pinfunction "1_P$1") (pintype "passive"))
      (node (ref "C221") (pin "P$1") (pinfunction "1_P$1") (pintype "passive"))
      (node (ref "C312") (pin "P$1") (pinfunction "1_P$1") (pintype "passive"))
      (node (ref "C321") (pin "P$1") (pinfunction "1_P$1") (pintype "passive"))
      (node (ref "C412") (pin "P$1") (pinfunction "1_P$1") (pintype "passive"))
      (node (ref "C421") (pin "P$1") (pinfunction "1_P$1") (pintype "passive"))
      (node (ref "C503") (pin "P$1") (pinfunction "1_P$1") (pintype "passive"))
      (node (ref "C603") (pin "P$1") (pinfunction "1_P$1") (pintype "passive"))
      (node (ref "C701") (pin "POS") (pinfunction "+_POS") (pintype "passive"))
      (node (ref "D101") (pin "POS") (pinfunction "+_POS") (pintype "bidirectional"))
      (node (ref "D201") (pin "POS") (pinfunction "+_POS") (pintype "bidirectional"))
      (node (ref "D301") (pin "POS") (pinfunction "+_POS") (pintype "bidirectional"))
      (node (ref "D401") (pin "POS") (pinfunction "+_POS") (pintype "bidirectional"))
      (node (ref "D501") (pin "POS") (pinfunction "+_POS") (pintype "bidirectional"))
      (node (ref "D502") (pin "1") (pinfunction "A_1") (pintype "passive"))
      (node (ref "D502") (pin "10") (pinfunction "A9_10") (pintype "passive"))
      (node (ref "D502") (pin "2") (pinfunction "A1_2") (pintype "passive"))
      (node (ref "D502") (pin "3") (pinfunction "A2_3") (pintype "passive"))
      (node (ref "D502") (pin "4") (pinfunction "A3_4") (pintype "passive"))
      (node (ref "D502") (pin "5") (pinfunction "A4_5") (pintype "passive"))
      (node (ref "D502") (pin "6") (pinfunction "A5_6") (pintype "passive"))
      (node (ref "D502") (pin "7") (pinfunction "A6_7") (pintype "passive"))
      (node (ref "D502") (pin "8") (pinfunction "A7_8") (pintype "passive"))
      (node (ref "D502") (pin "9") (pinfunction "A8_9") (pintype "passive"))
      (node (ref "D601") (pin "POS") (pinfunction "+_POS") (pintype "bidirectional"))
      (node (ref "D602") (pin "1") (pinfunction "A_1") (pintype "passive"))
      (node (ref "D602") (pin "10") (pinfunction "A9_10") (pintype "passive"))
      (node (ref "D602") (pin "2") (pinfunction "A1_2") (pintype "passive"))
      (node (ref "D602") (pin "3") (pinfunction "A2_3") (pintype "passive"))
      (node (ref "D602") (pin "4") (pinfunction "A3_4") (pintype "passive"))
      (node (ref "D602") (pin "5") (pinfunction "A4_5") (pintype "passive"))
      (node (ref "D602") (pin "6") (pinfunction "A5_6") (pintype "passive"))
      (node (ref "D602") (pin "7") (pinfunction "A6_7") (pintype "passive"))
      (node (ref "D602") (pin "8") (pinfunction "A7_8") (pintype "passive"))
      (node (ref "D602") (pin "9") (pinfunction "A8_9") (pintype "passive"))
      (node (ref "IC101") (pin "7") (pinfunction "V+_7") (pintype "bidirectional"))
      (node (ref "IC201") (pin "7") (pinfunction "V+_7") (pintype "bidirectional"))
      (node (ref "IC301") (pin "7") (pinfunction "V+_7") (pintype "bidirectional"))
      (node (ref "IC401") (pin "7") (pinfunction "V+_7") (pintype "bidirectional"))
      (node (ref "R701") (pin "P$1") (pinfunction "1_P$1") (pintype "passive"))
      (node (ref "R703") (pin "P$1") (pinfunction "1_P$1") (pintype "passive"))
      (node (ref "U1") (pin "8") (pinfunction "P$V+_8") (pintype "bidirectional"))
      (node (ref "U101") (pin "7") (pinfunction "P$V+_7") (pintype "bidirectional"))
      (node (ref "U201") (pin "7") (pinfunction "P$V+_7") (pintype "bidirectional"))
      (node (ref "U301") (pin "7") (pinfunction "P$V+_7") (pintype "bidirectional"))
      (node (ref "U401") (pin "7") (pinfunction "P$V+_7") (pintype "bidirectional"))
      (node (ref "U501") (pin "7") (pinfunction "P$V+_7") (pintype "bidirectional"))
      (node (ref "U502") (pin "3") (pinfunction "V+_3") (pintype "power_in"))
      (node (ref "U601") (pin "7") (pinfunction "P$V+_7") (pintype "bidirectional"))
      (node (ref "U602") (pin "3") (pinfunction "V+_3") (pintype "power_in"))
    )
    (net (code "194") (name "VNEG") (class "Default")
      (node (ref "C1") (pin "P$2") (pinfunction "2_P$2") (pintype "passive"))
      (node (ref "C113") (pin "P$1") (pinfunction "1_P$1") (pintype "passive"))
      (node (ref "C122") (pin "P$2") (pinfunction "2_P$2") (pintype "passive"))
      (node (ref "C213") (pin "P$1") (pinfunction "1_P$1") (pintype "passive"))
      (node (ref "C222") (pin "P$2") (pinfunction "2_P$2") (pintype "passive"))
      (node (ref "C313") (pin "P$1") (pinfunction "1_P$1") (pintype "passive"))
      (node (ref "C322") (pin "P$2") (pinfunction "2_P$2") (pintype "passive"))
      (node (ref "C413") (pin "P$1") (pinfunction "1_P$1") (pintype "passive"))
      (node (ref "C422") (pin "P$2") (pinfunction "2_P$2") (pintype "passive"))
      (node (ref "C504") (pin "P$2") (pinfunction "2_P$2") (pintype "passive"))
      (node (ref "C604") (pin "P$2") (pinfunction "2_P$2") (pintype "passive"))
      (node (ref "C702") (pin "NEG") (pinfunction "-_NEG") (pintype "passive"))
      (node (ref "D101") (pin "NEG") (pinfunction "-_NEG") (pintype "bidirectional"))
      (node (ref "D201") (pin "NEG") (pinfunction "-_NEG") (pintype "bidirectional"))
      (node (ref "D301") (pin "NEG") (pinfunction "-_NEG") (pintype "bidirectional"))
      (node (ref "D401") (pin "NEG") (pinfunction "-_NEG") (pintype "bidirectional"))
      (node (ref "D501") (pin "NEG") (pinfunction "-_NEG") (pintype "bidirectional"))
      (node (ref "D601") (pin "NEG") (pinfunction "-_NEG") (pintype "bidirectional"))
      (node (ref "IC101") (pin "4") (pinfunction "V-_4") (pintype "bidirectional"))
      (node (ref "IC201") (pin "4") (pinfunction "V-_4") (pintype "bidirectional"))
      (node (ref "IC301") (pin "4") (pinfunction "V-_4") (pintype "bidirectional"))
      (node (ref "IC401") (pin "4") (pinfunction "V-_4") (pintype "bidirectional"))
      (node (ref "R702") (pin "P$1") (pinfunction "1_P$1") (pintype "passive"))
      (node (ref "U1") (pin "4") (pinfunction "P$V-_4") (pintype "bidirectional"))
      (node (ref "U101") (pin "4") (pinfunction "P$V-_4") (pintype "bidirectional"))
      (node (ref "U201") (pin "4") (pinfunction "P$V-_4") (pintype "bidirectional"))
      (node (ref "U301") (pin "4") (pinfunction "P$V-_4") (pintype "bidirectional"))
      (node (ref "U401") (pin "4") (pinfunction "P$V-_4") (pintype "bidirectional"))
      (node (ref "U501") (pin "4") (pinfunction "P$V-_4") (pintype "bidirectional"))
      (node (ref "U601") (pin "4") (pinfunction "P$V-_4") (pintype "bidirectional"))
    )
    (net (code "195") (name "unconnected-(U502-MODE-Pad9)") (class "Default")
      (node (ref "U502") (pin "9") (pinfunction "MODE_9") (pintype "input"))
    )
    (net (code "196") (name "unconnected-(U602-MODE-Pad9)") (class "Default")
      (node (ref "U602") (pin "9") (pinfunction "MODE_9") (pintype "input"))
    )
  )
)
